# ADCS_Motherboard.net
KiCad netlist of a schematic drawn in EAGLE
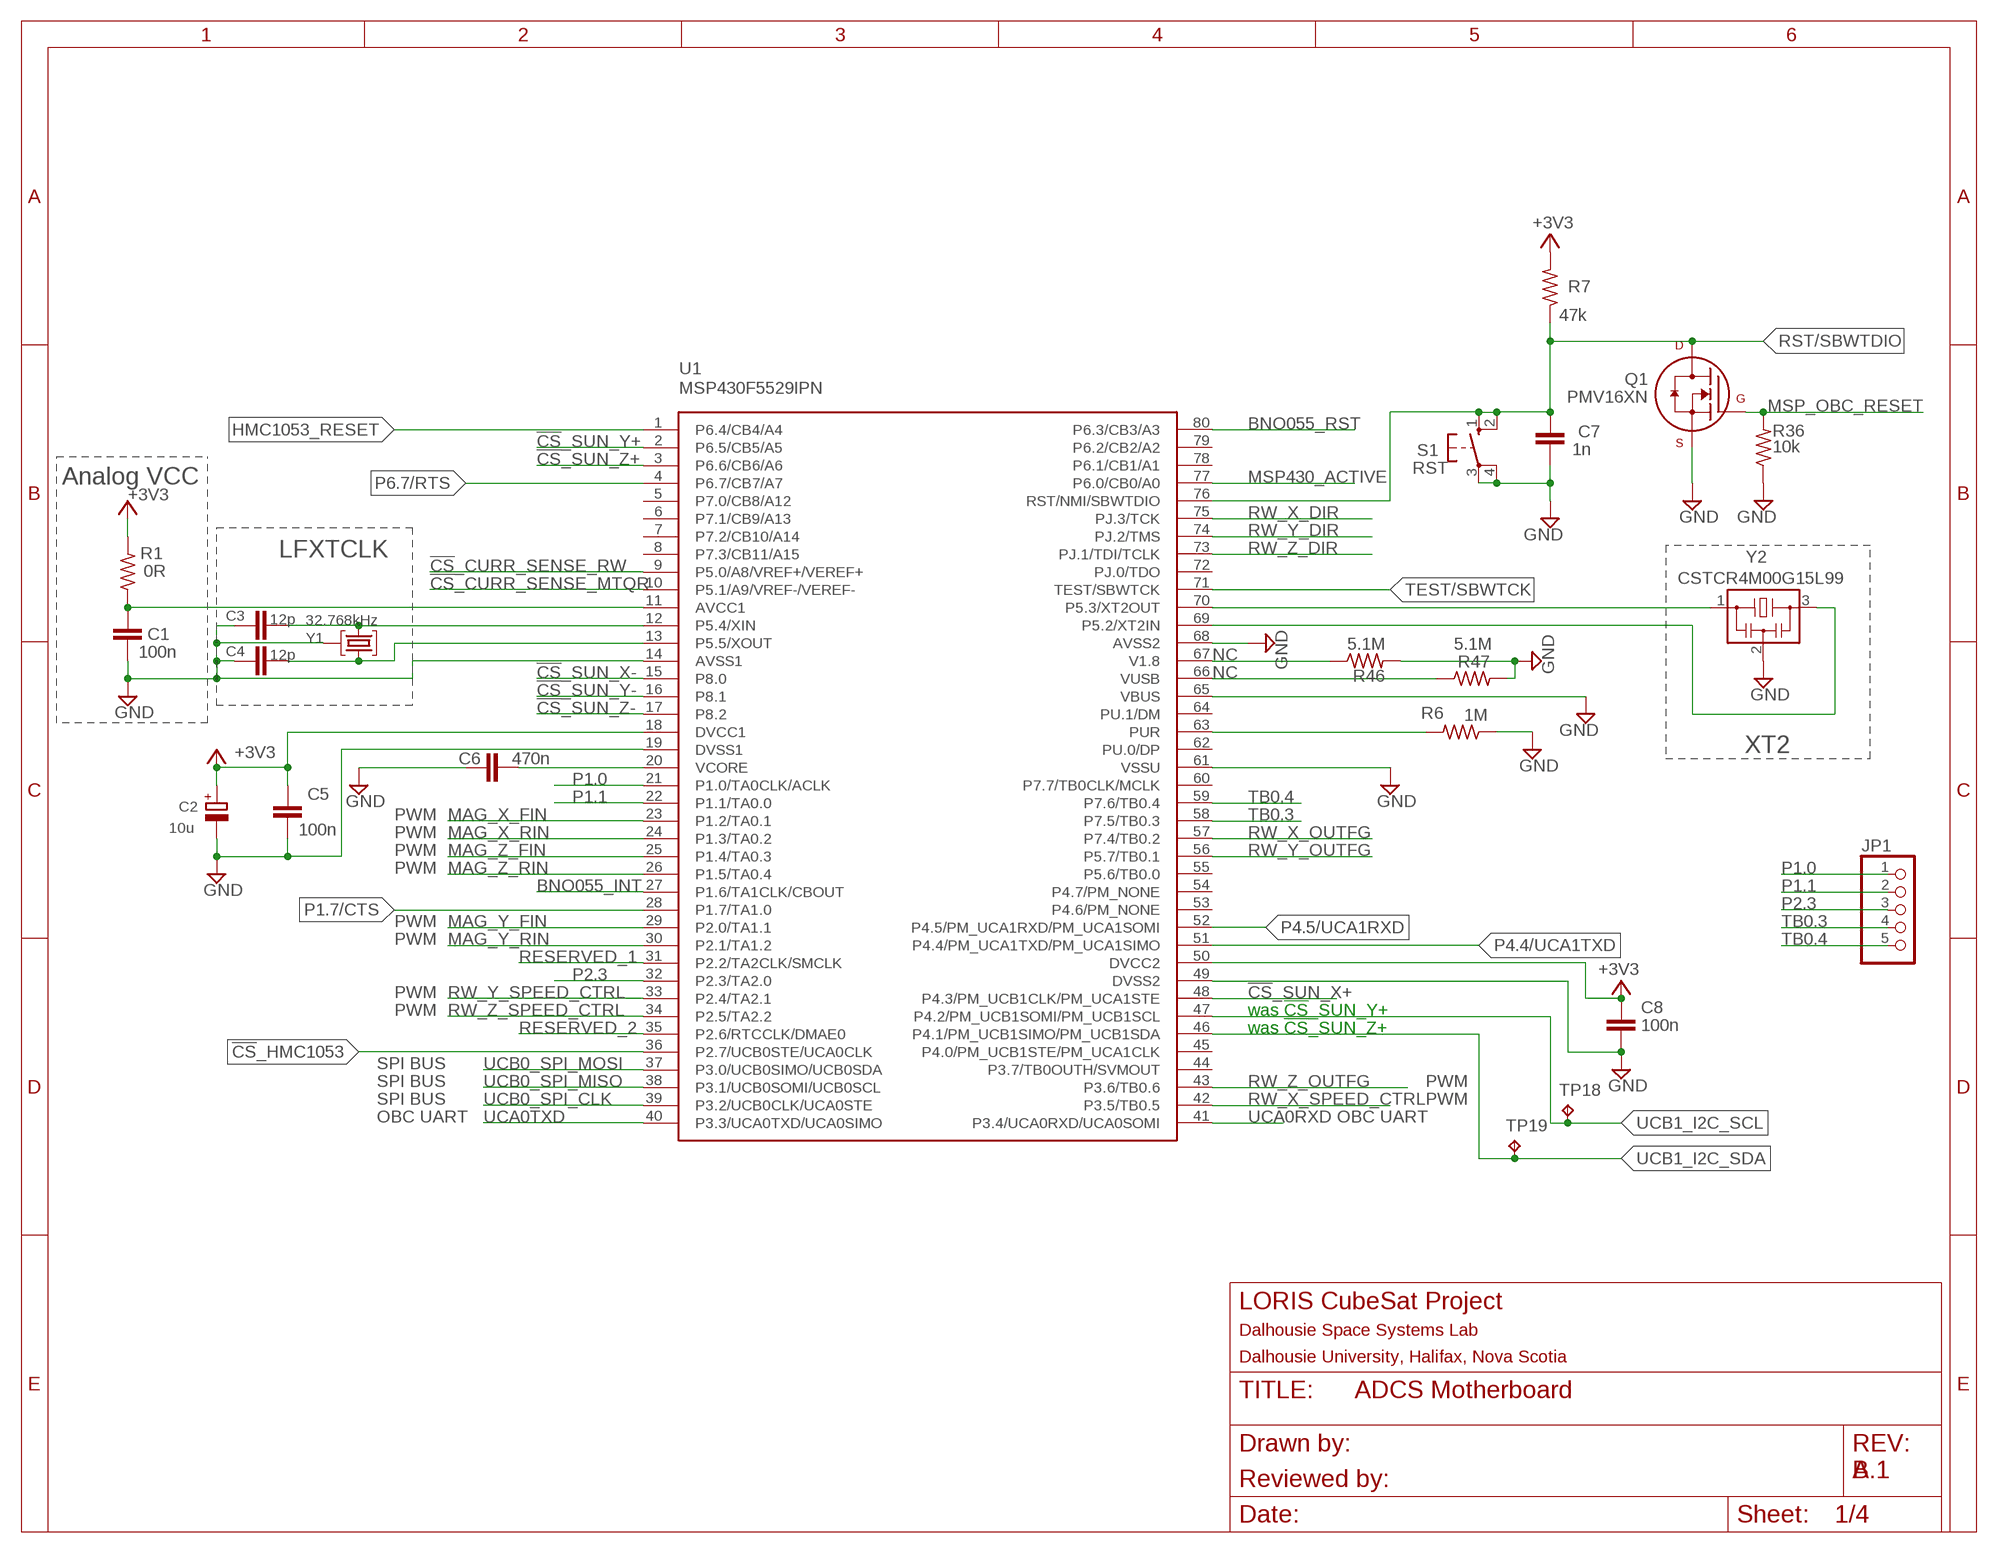
[diagram p0: schematic, sheet 1]
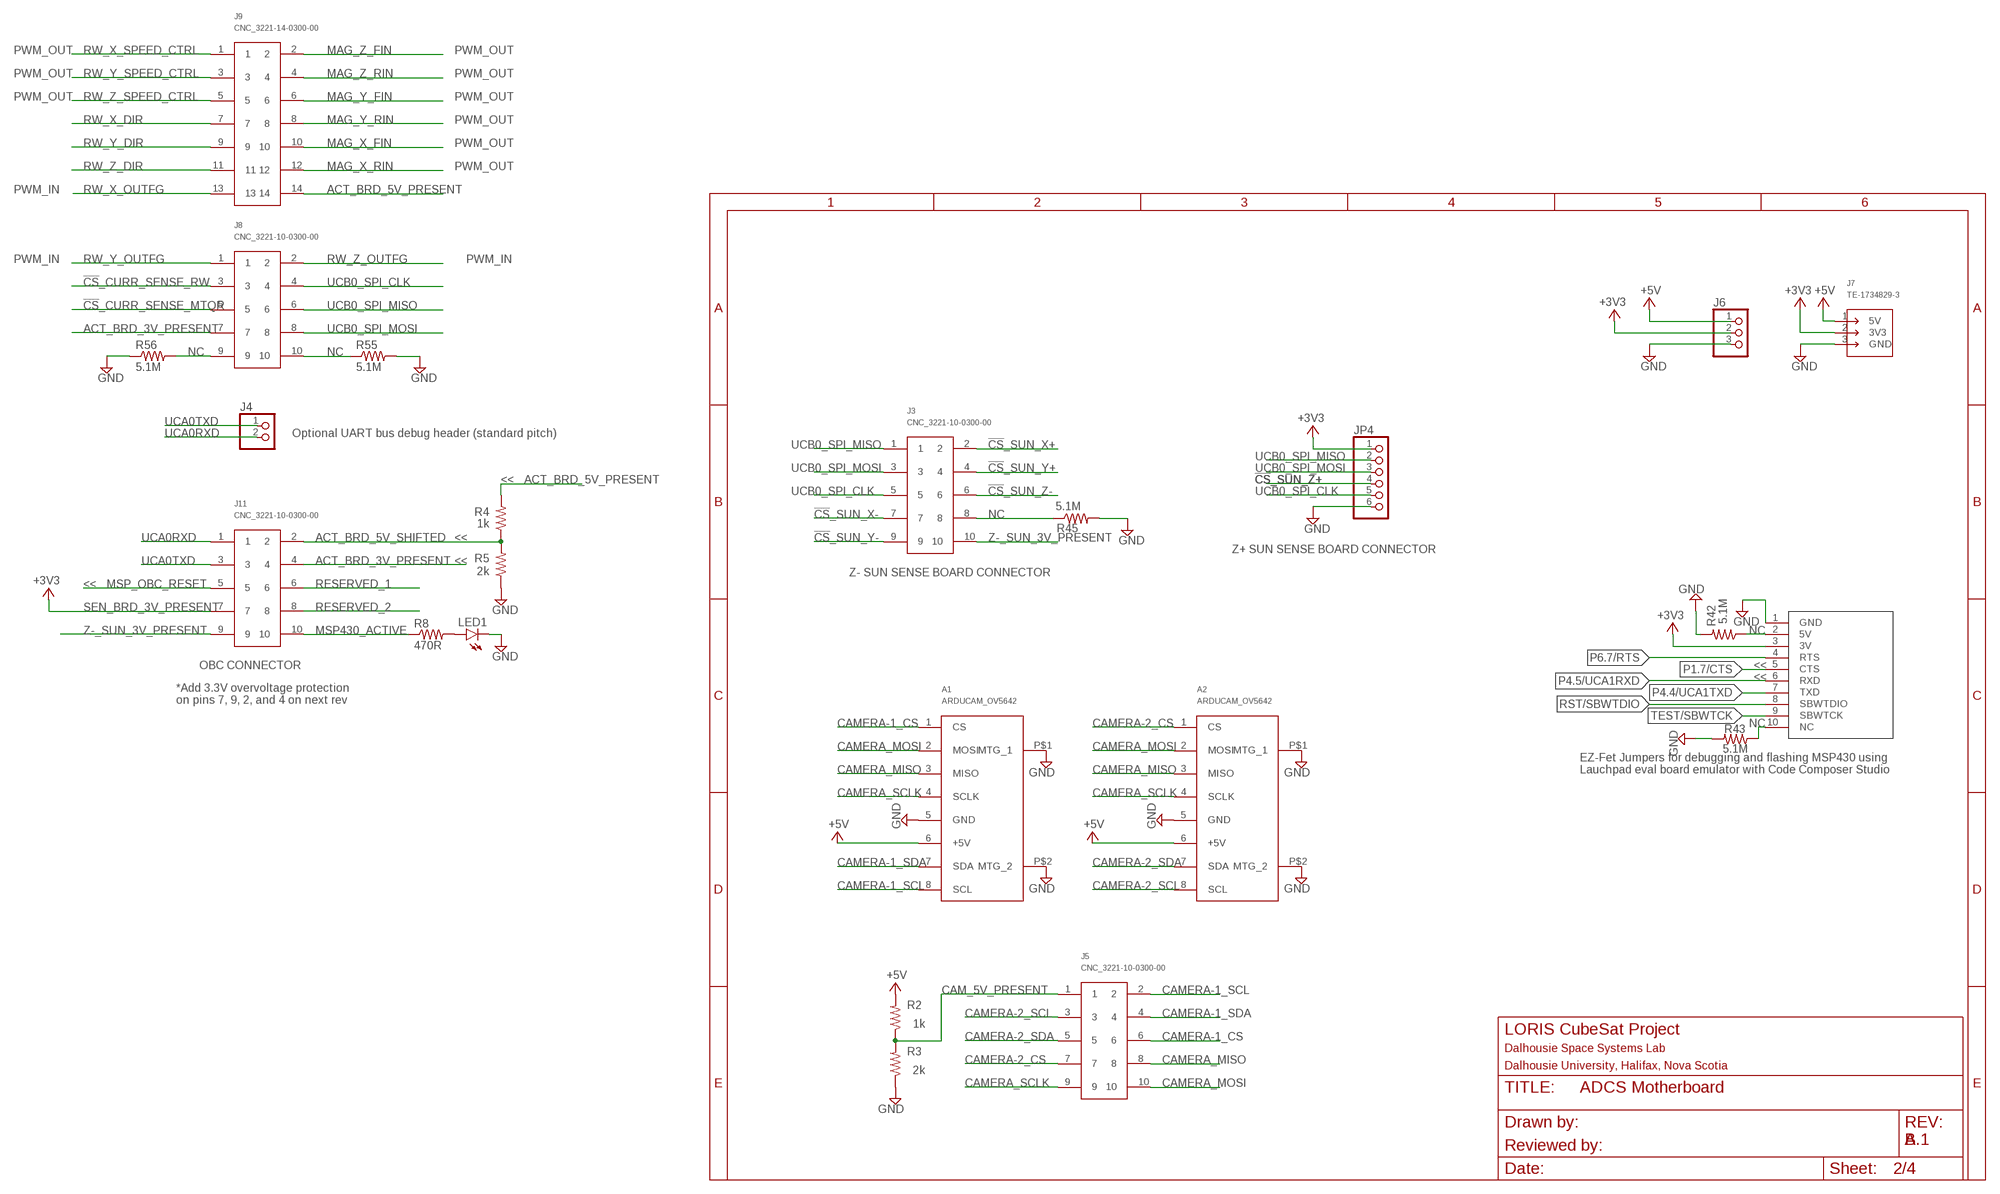
[diagram p1: schematic, sheet 2]
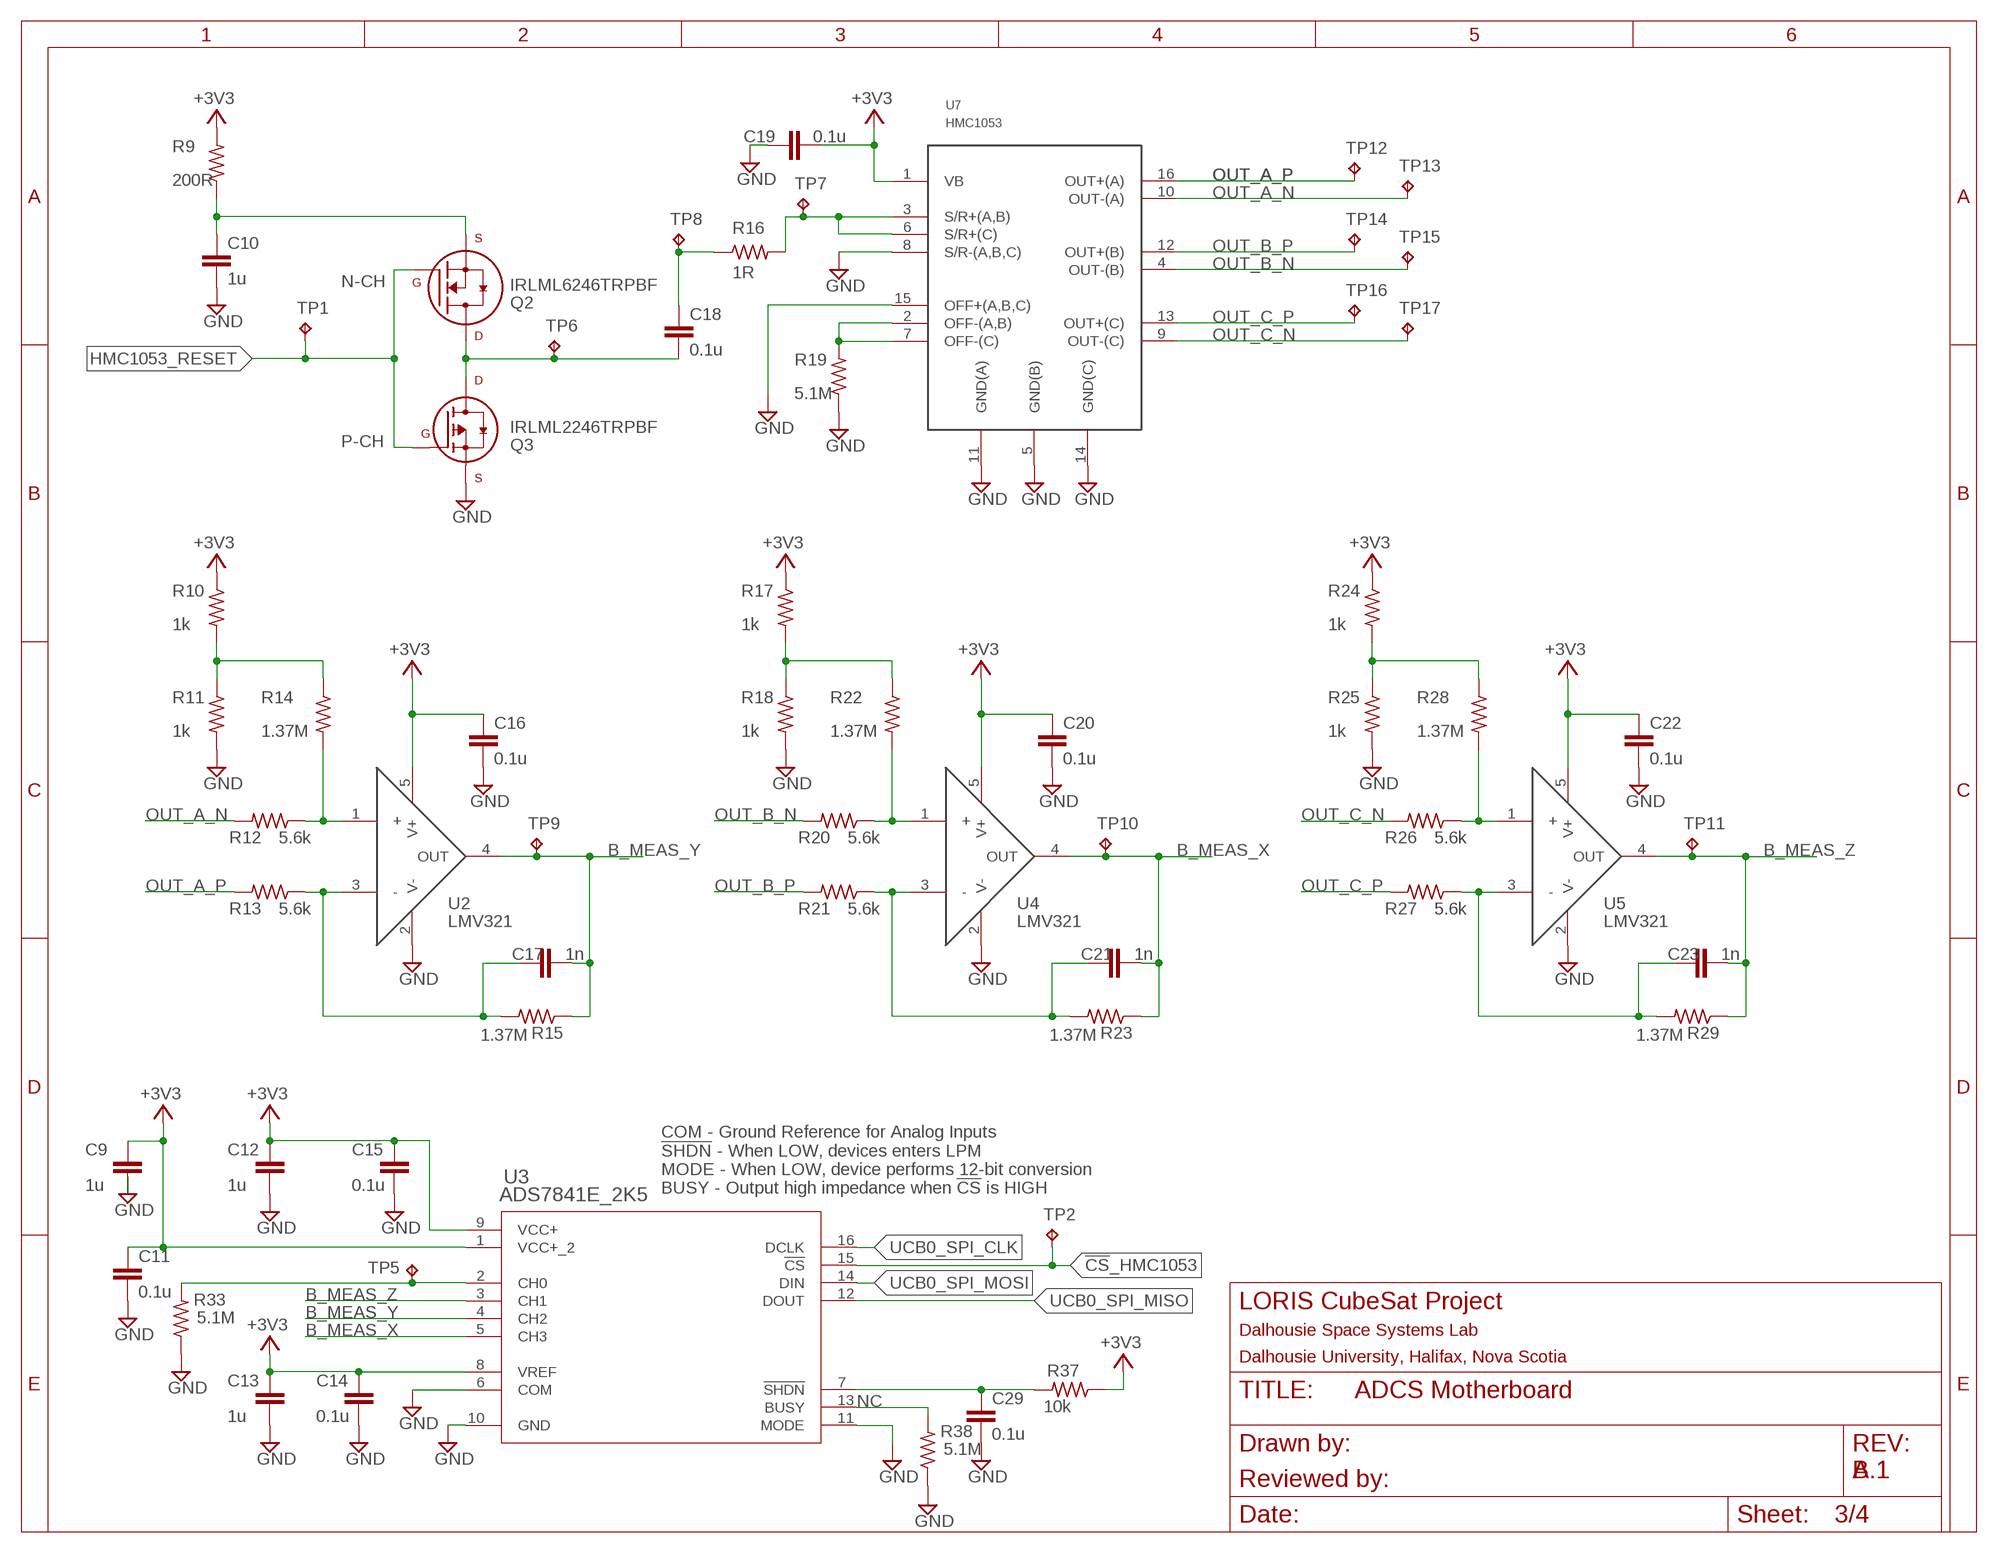
[diagram p2: schematic, sheet 3]
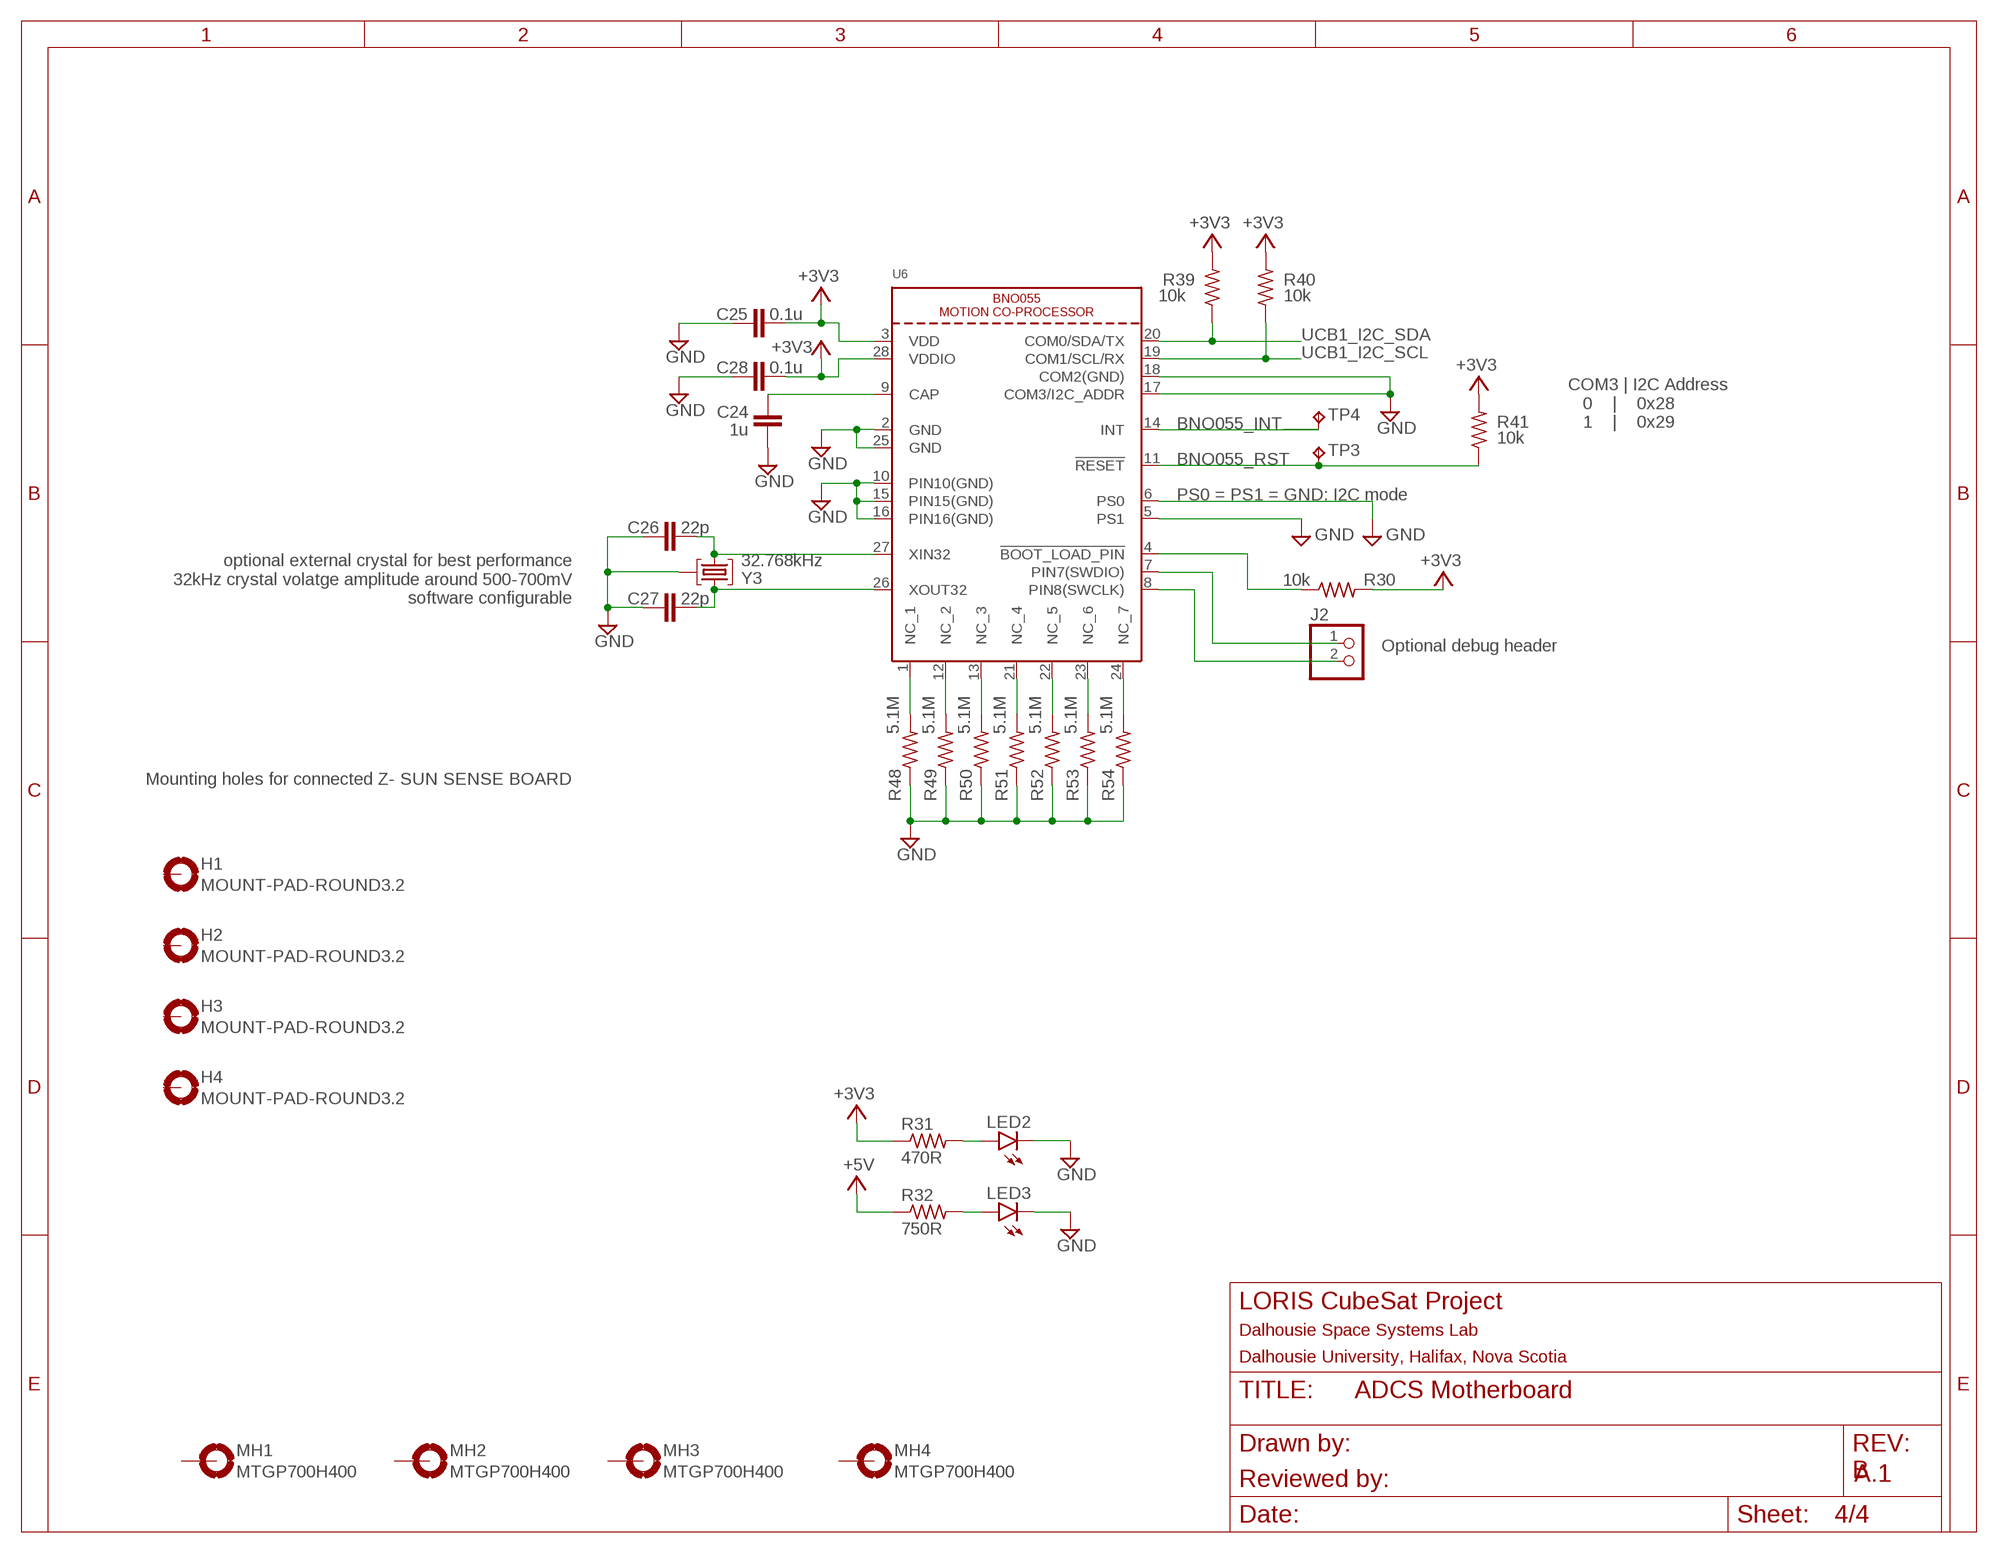
[diagram p3: schematic, sheet 4]

(export (version "E")
  (design (tool "Eeschema 10.0.6"))
  (components
    (comp (ref "C9")
      (value "1u")
      (footprint "eagle-import:C0805")
      (libsource (lib "eagle-import") (part "C-EUC0805"))
    )
    (comp (ref "C10")
      (value "1u")
      (footprint "eagle-import:C0603")
      (libsource (lib "eagle-import") (part "C-EUC0603"))
    )
    (comp (ref "C11")
      (value "0.1u")
      (footprint "eagle-import:C0603")
      (libsource (lib "eagle-import") (part "C-EUC0603"))
    )
    (comp (ref "C12")
      (value "1u")
      (footprint "eagle-import:C0805")
      (libsource (lib "eagle-import") (part "C-EUC0805"))
    )
    (comp (ref "C13")
      (value "1u")
      (footprint "eagle-import:C0805")
      (libsource (lib "eagle-import") (part "C-EUC0805"))
    )
    (comp (ref "C14")
      (value "0.1u")
      (footprint "eagle-import:C0603")
      (libsource (lib "eagle-import") (part "C-EUC0603"))
    )
    (comp (ref "C15")
      (value "0.1u")
      (footprint "eagle-import:C0603")
      (libsource (lib "eagle-import") (part "C-EUC0603"))
    )
    (comp (ref "C16")
      (value "0.1u")
      (footprint "eagle-import:C0603")
      (libsource (lib "eagle-import") (part "C-EUC0603"))
    )
    (comp (ref "C17")
      (value "1n")
      (footprint "eagle-import:C0603")
      (libsource (lib "eagle-import") (part "C-EUC0603"))
    )
    (comp (ref "C18")
      (value "0.1u")
      (footprint "eagle-import:C0805")
      (libsource (lib "eagle-import") (part "C-EUC0805"))
    )
    (comp (ref "C19")
      (value "0.1u")
      (footprint "eagle-import:C0603")
      (libsource (lib "eagle-import") (part "C-EUC0603"))
    )
    (comp (ref "C20")
      (value "0.1u")
      (footprint "eagle-import:C0603")
      (libsource (lib "eagle-import") (part "C-EUC0603"))
    )
    (comp (ref "C21")
      (value "1n")
      (footprint "eagle-import:C0603")
      (libsource (lib "eagle-import") (part "C-EUC0603"))
    )
    (comp (ref "C22")
      (value "0.1u")
      (footprint "eagle-import:C0603")
      (libsource (lib "eagle-import") (part "C-EUC0603"))
    )
    (comp (ref "C23")
      (value "1n")
      (footprint "eagle-import:C0603")
      (libsource (lib "eagle-import") (part "C-EUC0603"))
    )
    (comp (ref "C29")
      (value "0.1u")
      (footprint "eagle-import:C0603")
      (libsource (lib "eagle-import") (part "C-EUC0603"))
    )
    (comp (ref "Q2")
      (value "IRLML6246TRPBF")
      (footprint "eagle-import:SOT23-3P95_237X112L25X40N_MICRO3")
      (libsource (lib "eagle-import") (part "IRLML6246TRPBF"))
    )
    (comp (ref "Q3")
      (value "IRLML2246TRPBF")
      (footprint "eagle-import:SOT23-3P95_237X112L25X40N_MICRO3")
      (libsource (lib "eagle-import") (part "IRLML2246TRPBF"))
    )
    (comp (ref "R9")
      (value "200R")
      (footprint "eagle-import:R0805")
      (libsource (lib "eagle-import") (part "R-US_R0805"))
    )
    (comp (ref "R10")
      (value "1k")
      (footprint "eagle-import:R0603")
      (libsource (lib "eagle-import") (part "R-US_R0603"))
    )
    (comp (ref "R11")
      (value "1k")
      (footprint "eagle-import:R0603")
      (libsource (lib "eagle-import") (part "R-US_R0603"))
    )
    (comp (ref "R12")
      (value "5.6k")
      (footprint "eagle-import:R0603")
      (libsource (lib "eagle-import") (part "R-US_R0603"))
    )
    (comp (ref "R13")
      (value "5.6k")
      (footprint "eagle-import:R0603")
      (libsource (lib "eagle-import") (part "R-US_R0603"))
    )
    (comp (ref "R14")
      (value "1.37M")
      (footprint "eagle-import:R0603")
      (libsource (lib "eagle-import") (part "R-US_R0603"))
    )
    (comp (ref "R15")
      (value "1.37M")
      (footprint "eagle-import:R0603")
      (libsource (lib "eagle-import") (part "R-US_R0603"))
    )
    (comp (ref "R16")
      (value "1R")
      (footprint "eagle-import:R0805")
      (libsource (lib "eagle-import") (part "R-US_R0805"))
    )
    (comp (ref "R17")
      (value "1k")
      (footprint "eagle-import:R0603")
      (libsource (lib "eagle-import") (part "R-US_R0603"))
    )
    (comp (ref "R18")
      (value "1k")
      (footprint "eagle-import:R0603")
      (libsource (lib "eagle-import") (part "R-US_R0603"))
    )
    (comp (ref "R19")
      (value "5.1M")
      (footprint "eagle-import:R0805")
      (libsource (lib "eagle-import") (part "R-US_R0805"))
    )
    (comp (ref "R20")
      (value "5.6k")
      (footprint "eagle-import:R0603")
      (libsource (lib "eagle-import") (part "R-US_R0603"))
    )
    (comp (ref "R21")
      (value "5.6k")
      (footprint "eagle-import:R0603")
      (libsource (lib "eagle-import") (part "R-US_R0603"))
    )
    (comp (ref "R22")
      (value "1.37M")
      (footprint "eagle-import:R0603")
      (libsource (lib "eagle-import") (part "R-US_R0603"))
    )
    (comp (ref "R23")
      (value "1.37M")
      (footprint "eagle-import:R0603")
      (libsource (lib "eagle-import") (part "R-US_R0603"))
    )
    (comp (ref "R24")
      (value "1k")
      (footprint "eagle-import:R0603")
      (libsource (lib "eagle-import") (part "R-US_R0603"))
    )
    (comp (ref "R25")
      (value "1k")
      (footprint "eagle-import:R0603")
      (libsource (lib "eagle-import") (part "R-US_R0603"))
    )
    (comp (ref "R26")
      (value "5.6k")
      (footprint "eagle-import:R0603")
      (libsource (lib "eagle-import") (part "R-US_R0603"))
    )
    (comp (ref "R27")
      (value "5.6k")
      (footprint "eagle-import:R0603")
      (libsource (lib "eagle-import") (part "R-US_R0603"))
    )
    (comp (ref "R28")
      (value "1.37M")
      (footprint "eagle-import:R0603")
      (libsource (lib "eagle-import") (part "R-US_R0603"))
    )
    (comp (ref "R29")
      (value "1.37M")
      (footprint "eagle-import:R0603")
      (libsource (lib "eagle-import") (part "R-US_R0603"))
    )
    (comp (ref "R33")
      (value "5.1M")
      (footprint "eagle-import:R0402")
      (libsource (lib "eagle-import") (part "R-US_R0402"))
    )
    (comp (ref "R37")
      (value "10k")
      (footprint "eagle-import:R0805")
      (libsource (lib "eagle-import") (part "R-US_R0805"))
    )
    (comp (ref "R38")
      (value "5.1M")
      (footprint "eagle-import:R0402")
      (libsource (lib "eagle-import") (part "R-US_R0402"))
    )
    (comp (ref "TP1")
      (value "TESTPOINT")
      (footprint "eagle-import:TP_P76H50")
      (libsource (lib "eagle-import") (part "TESTPOINT"))
    )
    (comp (ref "TP2")
      (value "TESTPOINT")
      (footprint "eagle-import:TP_P76H50")
      (libsource (lib "eagle-import") (part "TESTPOINT"))
    )
    (comp (ref "TP5")
      (value "TESTPOINT")
      (footprint "eagle-import:TP_P76H50")
      (libsource (lib "eagle-import") (part "TESTPOINT"))
    )
    (comp (ref "TP6")
      (value "TESTPOINT")
      (footprint "eagle-import:TP_P76H50")
      (libsource (lib "eagle-import") (part "TESTPOINT"))
    )
    (comp (ref "TP7")
      (value "TESTPOINT")
      (footprint "eagle-import:TP_P76H50")
      (libsource (lib "eagle-import") (part "TESTPOINT"))
    )
    (comp (ref "TP8")
      (value "TESTPOINT")
      (footprint "eagle-import:TP_P76H50")
      (libsource (lib "eagle-import") (part "TESTPOINT"))
    )
    (comp (ref "TP9")
      (value "TESTPOINT")
      (footprint "eagle-import:TP_P76H50")
      (libsource (lib "eagle-import") (part "TESTPOINT"))
    )
    (comp (ref "TP10")
      (value "TESTPOINT")
      (footprint "eagle-import:TP_P76H50")
      (libsource (lib "eagle-import") (part "TESTPOINT"))
    )
    (comp (ref "TP11")
      (value "TESTPOINT")
      (footprint "eagle-import:TP_P76H50")
      (libsource (lib "eagle-import") (part "TESTPOINT"))
    )
    (comp (ref "TP12")
      (value "TESTPOINT")
      (footprint "eagle-import:TP_P76H50")
      (libsource (lib "eagle-import") (part "TESTPOINT"))
    )
    (comp (ref "TP13")
      (value "TESTPOINT")
      (footprint "eagle-import:TP_P76H50")
      (libsource (lib "eagle-import") (part "TESTPOINT"))
    )
    (comp (ref "TP14")
      (value "TESTPOINT")
      (footprint "eagle-import:TP_P76H50")
      (libsource (lib "eagle-import") (part "TESTPOINT"))
    )
    (comp (ref "TP15")
      (value "TESTPOINT")
      (footprint "eagle-import:TP_P76H50")
      (libsource (lib "eagle-import") (part "TESTPOINT"))
    )
    (comp (ref "TP16")
      (value "TESTPOINT")
      (footprint "eagle-import:TP_P76H50")
      (libsource (lib "eagle-import") (part "TESTPOINT"))
    )
    (comp (ref "TP17")
      (value "TESTPOINT")
      (footprint "eagle-import:TP_P76H50")
      (libsource (lib "eagle-import") (part "TESTPOINT"))
    )
    (comp (ref "U2")
      (value "LMV321")
      (footprint "eagle-import:SC70-5P65_210X110L36X22N")
      (libsource (lib "eagle-import") (part "LMV321"))
    )
    (comp (ref "U3")
      (value "ADS7841E_2K5")
      (footprint "eagle-import:DBQ16")
      (fields
        (field (name "GENERIC_PART_NUMBER") "ADS7841")
        (field (name "MANUFACTURER") "Texas Instruments")
      )
      (libsource (lib "eagle-import") (part "ADS7841E_2K5"))
    )
    (comp (ref "U4")
      (value "LMV321")
      (footprint "eagle-import:SC70-5P65_210X110L36X22N")
      (libsource (lib "eagle-import") (part "LMV321"))
    )
    (comp (ref "U5")
      (value "LMV321")
      (footprint "eagle-import:SC70-5P65_210X110L36X22N")
      (libsource (lib "eagle-import") (part "LMV321"))
    )
    (comp (ref "U7")
      (value "HMC1053")
      (footprint "eagle-import:LCCS16P127_736X736X279L127X50N")
      (libsource (lib "eagle-import") (part "HMC1053"))
    )
    (comp (ref "C1")
      (value "100n")
      (footprint "eagle-import:C0402")
      (libsource (lib "eagle-import") (part "C-EUC0402"))
    )
    (comp (ref "C2")
      (value "10u")
      (footprint "eagle-import:A_3216-18R")
      (libsource (lib "eagle-import") (part "POLARIZED_CAP"))
    )
    (comp (ref "C3")
      (value "12p")
      (footprint "eagle-import:C0402")
      (libsource (lib "eagle-import") (part "C-EUC0402"))
    )
    (comp (ref "C4")
      (value "12p")
      (footprint "eagle-import:C0402")
      (libsource (lib "eagle-import") (part "C-EUC0402"))
    )
    (comp (ref "C5")
      (value "100n")
      (footprint "eagle-import:C0402")
      (libsource (lib "eagle-import") (part "C-EUC0402"))
    )
    (comp (ref "C6")
      (value "470n")
      (footprint "eagle-import:C0402")
      (libsource (lib "eagle-import") (part "C-EUC0402"))
    )
    (comp (ref "C7")
      (value "1n")
      (footprint "eagle-import:C0402")
      (libsource (lib "eagle-import") (part "C-EUC0402"))
    )
    (comp (ref "C8")
      (value "100n")
      (footprint "eagle-import:C0402")
      (libsource (lib "eagle-import") (part "C-EUC0402"))
    )
    (comp (ref "JP1")
      (value "PINHD-1X5")
      (footprint "eagle-import:1X05")
      (libsource (lib "eagle-import") (part "PINHD-1X5"))
    )
    (comp (ref "Q1")
      (value "PMV16XN")
      (footprint "eagle-import:SOT23-3P95_230X110L20X43N_PMV16XN")
      (libsource (lib "eagle-import") (part "PMV16XN"))
    )
    (comp (ref "R1")
      (value "0R")
      (footprint "eagle-import:R0402")
      (libsource (lib "eagle-import") (part "R-US_R0402"))
    )
    (comp (ref "R6")
      (value "1M")
      (footprint "eagle-import:R0603")
      (libsource (lib "eagle-import") (part "R-US_R0603"))
    )
    (comp (ref "R7")
      (value "47k")
      (footprint "eagle-import:R0402")
      (libsource (lib "eagle-import") (part "R-US_R0402"))
    )
    (comp (ref "R36")
      (value "10k")
      (footprint "eagle-import:R0603")
      (libsource (lib "eagle-import") (part "R-US_R0603"))
    )
    (comp (ref "R46")
      (value "5.1M")
      (footprint "eagle-import:R0402")
      (libsource (lib "eagle-import") (part "R-US_R0402"))
    )
    (comp (ref "R47")
      (value "5.1M")
      (footprint "eagle-import:R0402")
      (libsource (lib "eagle-import") (part "R-US_R0402"))
    )
    (comp (ref "S1")
      (value "RST")
      (footprint "eagle-import:B3F-10XX")
      (fields (field (name "MPN") "B3F-1000"))
      (libsource (lib "eagle-import") (part "10-XX"))
    )
    (comp (ref "TP18")
      (value "TESTPOINT")
      (footprint "eagle-import:TP_P76H50")
      (libsource (lib "eagle-import") (part "TESTPOINT"))
    )
    (comp (ref "TP19")
      (value "TESTPOINT")
      (footprint "eagle-import:TP_P76H50")
      (libsource (lib "eagle-import") (part "TESTPOINT"))
    )
    (comp (ref "U1")
      (value "MSP430F5529IPN")
      (footprint "eagle-import:QFP80P50_1400X1400X160L60X22N")
      (libsource (lib "eagle-import") (part "MSP430F5529IPN"))
    )
    (comp (ref "Y1")
      (value "32.768kHz")
      (footprint "eagle-import:MS3V-T1R")
      (libsource (lib "eagle-import") (part "MS3V-T1R"))
    )
    (comp (ref "Y2")
      (value "CSTCR4M00G15L99")
      (footprint "eagle-import:MURATA-FILTER_CSTCR")
      (fields (field (name "MPN") "CSTCR6M00G53-R0"))
      (libsource (lib "eagle-import") (part "CSTCR4M00G15L996M00G53Z"))
    )
    (comp (ref "C24")
      (value "1u")
      (footprint "eagle-import:C0402")
      (libsource (lib "eagle-import") (part "C-EUC0402"))
    )
    (comp (ref "C25")
      (value "0.1u")
      (footprint "eagle-import:C0402")
      (libsource (lib "eagle-import") (part "C-EUC0402"))
    )
    (comp (ref "C26")
      (value "22p")
      (footprint "eagle-import:C0402")
      (libsource (lib "eagle-import") (part "C-EUC0402"))
    )
    (comp (ref "C27")
      (value "22p")
      (footprint "eagle-import:C0402")
      (libsource (lib "eagle-import") (part "C-EUC0402"))
    )
    (comp (ref "C28")
      (value "0.1u")
      (footprint "eagle-import:C0402")
      (libsource (lib "eagle-import") (part "C-EUC0402"))
    )
    (comp (ref "H1")
      (value "MOUNT-PAD-ROUND3.2")
      (footprint "eagle-import:3,2-PAD")
      (libsource (lib "eagle-import") (part "MOUNT-PAD-ROUND3.2"))
    )
    (comp (ref "H2")
      (value "MOUNT-PAD-ROUND3.2")
      (footprint "eagle-import:3,2-PAD")
      (libsource (lib "eagle-import") (part "MOUNT-PAD-ROUND3.2"))
    )
    (comp (ref "H3")
      (value "MOUNT-PAD-ROUND3.2")
      (footprint "eagle-import:3,2-PAD")
      (libsource (lib "eagle-import") (part "MOUNT-PAD-ROUND3.2"))
    )
    (comp (ref "H4")
      (value "MOUNT-PAD-ROUND3.2")
      (footprint "eagle-import:3,2-PAD")
      (libsource (lib "eagle-import") (part "MOUNT-PAD-ROUND3.2"))
    )
    (comp (ref "J2")
      (value "HDR_1X2_")
      (footprint "eagle-import:1X02")
      (libsource (lib "eagle-import") (part "HDR_1X2_"))
    )
    (comp (ref "LED2")
      (value "LEDCHIP-LED0603")
      (footprint "eagle-import:CHIP-LED0603")
      (libsource (lib "eagle-import") (part "LEDCHIP-LED0603"))
    )
    (comp (ref "LED3")
      (value "LEDCHIP-LED0603")
      (footprint "eagle-import:CHIP-LED0603")
      (libsource (lib "eagle-import") (part "LEDCHIP-LED0603"))
    )
    (comp (ref "MH1")
      (value "MTGP700H400")
      (footprint "eagle-import:MTGP700H400")
      (libsource (lib "eagle-import") (part "MTGP700H400"))
    )
    (comp (ref "MH2")
      (value "MTGP700H400")
      (footprint "eagle-import:MTGP700H400")
      (libsource (lib "eagle-import") (part "MTGP700H400"))
    )
    (comp (ref "MH3")
      (value "MTGP700H400")
      (footprint "eagle-import:MTGP700H400")
      (libsource (lib "eagle-import") (part "MTGP700H400"))
    )
    (comp (ref "MH4")
      (value "MTGP700H400")
      (footprint "eagle-import:MTGP700H400")
      (libsource (lib "eagle-import") (part "MTGP700H400"))
    )
    (comp (ref "R30")
      (value "10k")
      (footprint "eagle-import:R0402")
      (libsource (lib "eagle-import") (part "R-US_R0402"))
    )
    (comp (ref "R31")
      (value "470R")
      (footprint "eagle-import:R0603")
      (libsource (lib "eagle-import") (part "R-US_R0603"))
    )
    (comp (ref "R32")
      (value "750R")
      (footprint "eagle-import:R0603")
      (libsource (lib "eagle-import") (part "R-US_R0603"))
    )
    (comp (ref "R39")
      (value "10k")
      (footprint "eagle-import:R0402")
      (libsource (lib "eagle-import") (part "R-US_R0402"))
    )
    (comp (ref "R40")
      (value "10k")
      (footprint "eagle-import:R0402")
      (libsource (lib "eagle-import") (part "R-US_R0402"))
    )
    (comp (ref "R41")
      (value "10k")
      (footprint "eagle-import:R0402")
      (libsource (lib "eagle-import") (part "R-US_R0402"))
    )
    (comp (ref "R48")
      (value "5.1M")
      (footprint "eagle-import:R0402")
      (libsource (lib "eagle-import") (part "R-US_R0402"))
    )
    (comp (ref "R49")
      (value "5.1M")
      (footprint "eagle-import:R0402")
      (libsource (lib "eagle-import") (part "R-US_R0402"))
    )
    (comp (ref "R50")
      (value "5.1M")
      (footprint "eagle-import:R0402")
      (libsource (lib "eagle-import") (part "R-US_R0402"))
    )
    (comp (ref "R51")
      (value "5.1M")
      (footprint "eagle-import:R0402")
      (libsource (lib "eagle-import") (part "R-US_R0402"))
    )
    (comp (ref "R52")
      (value "5.1M")
      (footprint "eagle-import:R0402")
      (libsource (lib "eagle-import") (part "R-US_R0402"))
    )
    (comp (ref "R53")
      (value "5.1M")
      (footprint "eagle-import:R0402")
      (libsource (lib "eagle-import") (part "R-US_R0402"))
    )
    (comp (ref "R54")
      (value "5.1M")
      (footprint "eagle-import:R0402")
      (libsource (lib "eagle-import") (part "R-US_R0402"))
    )
    (comp (ref "TP3")
      (value "TESTPOINT")
      (footprint "eagle-import:TP_P76H50")
      (libsource (lib "eagle-import") (part "TESTPOINT"))
    )
    (comp (ref "TP4")
      (value "TESTPOINT")
      (footprint "eagle-import:TP_P76H50")
      (libsource (lib "eagle-import") (part "TESTPOINT"))
    )
    (comp (ref "U6")
      (value "BNO055")
      (footprint "eagle-import:BNO055")
      (libsource (lib "eagle-import") (part "BNO055"))
    )
    (comp (ref "Y3")
      (value "32.768kHz")
      (footprint "eagle-import:MS3V-T1R")
      (libsource (lib "eagle-import") (part "MS3V-T1R"))
    )
    (comp (ref "A1")
      (value "ARDUCAM_OV5642")
      (footprint "eagle-import:ARDUCAM")
      (libsource (lib "eagle-import") (part "ARDUCAM_OV5642"))
    )
    (comp (ref "A2")
      (value "ARDUCAM_OV5642")
      (footprint "eagle-import:ARDUCAM")
      (libsource (lib "eagle-import") (part "ARDUCAM_OV5642"))
    )
    (comp (ref "J1")
      (value "HDR_10_EZFET_DEBUGGER")
      (footprint "eagle-import:HDRV10W66P254_10X1_2540X254H858")
      (libsource (lib "eagle-import") (part "HDR_10_EZFET_DEBUGGER"))
    )
    (comp (ref "J3")
      (value "CNC_3221-10-0300-00")
      (footprint "eagle-import:CNC_3221-10-0300-00")
      (libsource (lib "eagle-import") (part "CNC_3221-10-0300-00"))
    )
    (comp (ref "J4")
      (value "HDR_1X2_")
      (footprint "eagle-import:1X02")
      (libsource (lib "eagle-import") (part "HDR_1X2_"))
    )
    (comp (ref "J5")
      (value "CNC_3221-10-0300-00")
      (footprint "eagle-import:CNC_3221-10-0300-00")
      (libsource (lib "eagle-import") (part "CNC_3221-10-0300-00"))
    )
    (comp (ref "J6")
      (value "PINHD-1X3")
      (footprint "eagle-import:1X03")
      (libsource (lib "eagle-import") (part "PINHD-1X3"))
    )
    (comp (ref "J7")
      (value "TE-1734829-3")
      (footprint "eagle-import:TE-1734829-3")
      (libsource (lib "eagle-import") (part "TE-1734829-3"))
    )
    (comp (ref "J8")
      (value "CNC_3221-10-0300-00")
      (footprint "eagle-import:CNC_3221-10-0300-00")
      (libsource (lib "eagle-import") (part "CNC_3221-10-0300-00"))
    )
    (comp (ref "J9")
      (value "CNC_3221-14-0300-00")
      (footprint "eagle-import:CNC_3221-14-0300-00")
      (libsource (lib "eagle-import") (part "CNC_3221-14-0300-00"))
    )
    (comp (ref "J11")
      (value "CNC_3221-10-0300-00")
      (footprint "eagle-import:CNC_3221-10-0300-00")
      (libsource (lib "eagle-import") (part "CNC_3221-10-0300-00"))
    )
    (comp (ref "JP4")
      (value "PINHD-1X6")
      (footprint "eagle-import:1X06")
      (libsource (lib "eagle-import") (part "PINHD-1X6"))
    )
    (comp (ref "LED1")
      (value "LEDCHIP-LED0603")
      (footprint "eagle-import:CHIP-LED0603")
      (libsource (lib "eagle-import") (part "LEDCHIP-LED0603"))
    )
    (comp (ref "R2")
      (value "1k")
      (footprint "eagle-import:R0603")
      (libsource (lib "eagle-import") (part "R-US_R0603"))
    )
    (comp (ref "R3")
      (value "2k")
      (footprint "eagle-import:R0603")
      (libsource (lib "eagle-import") (part "R-US_R0603"))
    )
    (comp (ref "R4")
      (value "1k")
      (footprint "eagle-import:R0603")
      (libsource (lib "eagle-import") (part "R-US_R0603"))
    )
    (comp (ref "R5")
      (value "2k")
      (footprint "eagle-import:R0603")
      (libsource (lib "eagle-import") (part "R-US_R0603"))
    )
    (comp (ref "R8")
      (value "470R")
      (footprint "eagle-import:R0603")
      (libsource (lib "eagle-import") (part "R-US_R0603"))
    )
    (comp (ref "R42")
      (value "5.1M")
      (footprint "eagle-import:R0402")
      (libsource (lib "eagle-import") (part "R-US_R0402"))
    )
    (comp (ref "R43")
      (value "5.1M")
      (footprint "eagle-import:R0402")
      (libsource (lib "eagle-import") (part "R-US_R0402"))
    )
    (comp (ref "R45")
      (value "5.1M")
      (footprint "eagle-import:R0402")
      (libsource (lib "eagle-import") (part "R-US_R0402"))
    )
    (comp (ref "R55")
      (value "5.1M")
      (footprint "eagle-import:R0603")
      (libsource (lib "eagle-import") (part "R-US_R0603"))
    )
    (comp (ref "R56")
      (value "5.1M")
      (footprint "eagle-import:R0603")
      (libsource (lib "eagle-import") (part "R-US_R0603"))
    )
  )
  (nets
    (net (code "1") (name "+3V3") (class "Default")
      (node (ref "C11") (pin "1") (pinfunction "1_1") (pintype "passive"))
      (node (ref "C12") (pin "1") (pinfunction "1_1") (pintype "passive"))
      (node (ref "C13") (pin "1") (pinfunction "1_1") (pintype "passive"))
      (node (ref "C14") (pin "1") (pinfunction "1_1") (pintype "passive"))
      (node (ref "C15") (pin "1") (pinfunction "1_1") (pintype "passive"))
      (node (ref "C16") (pin "1") (pinfunction "1_1") (pintype "passive"))
      (node (ref "C19") (pin "1") (pinfunction "1_1") (pintype "passive"))
      (node (ref "C2") (pin "+") (pinfunction "+_+") (pintype "passive"))
      (node (ref "C20") (pin "1") (pinfunction "1_1") (pintype "passive"))
      (node (ref "C22") (pin "1") (pinfunction "1_1") (pintype "passive"))
      (node (ref "C25") (pin "2") (pinfunction "2_2") (pintype "passive"))
      (node (ref "C28") (pin "2") (pinfunction "2_2") (pintype "passive"))
      (node (ref "C5") (pin "2") (pinfunction "2_2") (pintype "passive"))
      (node (ref "C8") (pin "1") (pinfunction "1_1") (pintype "passive"))
      (node (ref "C9") (pin "1") (pinfunction "1_1") (pintype "passive"))
      (node (ref "J1") (pin "3") (pinfunction "3V_3") (pintype "bidirectional"))
      (node (ref "J11") (pin "7") (pinfunction "7_7") (pintype "bidirectional"))
      (node (ref "J6") (pin "2") (pinfunction "2_2") (pintype "passive"))
      (node (ref "J7") (pin "2") (pinfunction "3V3_2") (pintype "bidirectional"))
      (node (ref "JP4") (pin "1") (pinfunction "1_1") (pintype "passive"))
      (node (ref "R1") (pin "2") (pinfunction "2_2") (pintype "passive"))
      (node (ref "R10") (pin "1") (pinfunction "1_1") (pintype "passive"))
      (node (ref "R17") (pin "1") (pinfunction "1_1") (pintype "passive"))
      (node (ref "R24") (pin "1") (pinfunction "1_1") (pintype "passive"))
      (node (ref "R30") (pin "2") (pinfunction "2_2") (pintype "passive"))
      (node (ref "R31") (pin "1") (pinfunction "1_1") (pintype "passive"))
      (node (ref "R37") (pin "1") (pinfunction "1_1") (pintype "passive"))
      (node (ref "R39") (pin "2") (pinfunction "2_2") (pintype "passive"))
      (node (ref "R40") (pin "2") (pinfunction "2_2") (pintype "passive"))
      (node (ref "R41") (pin "2") (pinfunction "2_2") (pintype "passive"))
      (node (ref "R7") (pin "2") (pinfunction "2_2") (pintype "passive"))
      (node (ref "R9") (pin "2") (pinfunction "2_2") (pintype "passive"))
      (node (ref "U1") (pin "18") (pinfunction "DVCC1_18") (pintype "bidirectional"))
      (node (ref "U1") (pin "50") (pinfunction "DVCC2_50") (pintype "bidirectional"))
      (node (ref "U2") (pin "5") (pinfunction "V+_5") (pintype "bidirectional"))
      (node (ref "U3") (pin "1") (pinfunction "VCC+_2_1") (pintype "power_in"))
      (node (ref "U3") (pin "8") (pinfunction "VREF_8") (pintype "input"))
      (node (ref "U3") (pin "9") (pinfunction "VCC+_9") (pintype "power_in"))
      (node (ref "U4") (pin "5") (pinfunction "V+_5") (pintype "bidirectional"))
      (node (ref "U5") (pin "5") (pinfunction "V+_5") (pintype "bidirectional"))
      (node (ref "U6") (pin "28") (pinfunction "VDDIO_28") (pintype "power_in"))
      (node (ref "U6") (pin "3") (pinfunction "VDD_3") (pintype "power_in"))
      (node (ref "U7") (pin "1") (pinfunction "VB_1") (pintype "bidirectional"))
    )
    (net (code "2") (name "+5V") (class "Default")
      (node (ref "A1") (pin "6") (pinfunction "+5V_6") (pintype "bidirectional"))
      (node (ref "A2") (pin "6") (pinfunction "+5V_6") (pintype "bidirectional"))
      (node (ref "J6") (pin "1") (pinfunction "1_1") (pintype "passive"))
      (node (ref "J7") (pin "1") (pinfunction "5V_1") (pintype "bidirectional"))
      (node (ref "R2") (pin "2") (pinfunction "2_2") (pintype "passive"))
      (node (ref "R32") (pin "1") (pinfunction "1_1") (pintype "passive"))
    )
    (net (code "3") (name "ACT_BRD_3V_PRESENT") (class "Default")
      (node (ref "J11") (pin "4") (pinfunction "4_4") (pintype "bidirectional"))
      (node (ref "J8") (pin "7") (pinfunction "7_7") (pintype "bidirectional"))
    )
    (net (code "4") (name "ACT_BRD_5V_PRESENT") (class "Default")
      (node (ref "J9") (pin "14") (pinfunction "14_14") (pintype "bidirectional"))
      (node (ref "R4") (pin "2") (pinfunction "2_2") (pintype "passive"))
    )
    (net (code "5") (name "ACT_BRD_5V_SHIFTED") (class "Default")
      (node (ref "J11") (pin "2") (pinfunction "2_2") (pintype "bidirectional"))
      (node (ref "R4") (pin "1") (pinfunction "1_1") (pintype "passive"))
      (node (ref "R5") (pin "2") (pinfunction "2_2") (pintype "passive"))
    )
    (net (code "6") (name "BNO055_INT") (class "Default")
      (node (ref "TP4") (pin "1") (pinfunction "TP_1") (pintype "input"))
      (node (ref "U1") (pin "27") (pinfunction "P1.6/TA1CLK/CBOUT_27") (pintype "bidirectional"))
      (node (ref "U6") (pin "14") (pinfunction "INT_14") (pintype "output"))
    )
    (net (code "7") (name "BNO055_RST") (class "Default")
      (node (ref "R41") (pin "1") (pinfunction "1_1") (pintype "passive"))
      (node (ref "TP3") (pin "1") (pinfunction "TP_1") (pintype "input"))
      (node (ref "U1") (pin "80") (pinfunction "P6.3/CB3/A3_80") (pintype "bidirectional"))
      (node (ref "U6") (pin "11") (pinfunction "~{RESET}_11") (pintype "bidirectional"))
    )
    (net (code "8") (name "B_MEAS_X") (class "Default")
      (node (ref "C21") (pin "2") (pinfunction "2_2") (pintype "passive"))
      (node (ref "R23") (pin "1") (pinfunction "1_1") (pintype "passive"))
      (node (ref "TP10") (pin "1") (pinfunction "TP_1") (pintype "input"))
      (node (ref "U3") (pin "5") (pinfunction "CH3_5") (pintype "input"))
      (node (ref "U4") (pin "4") (pinfunction "OUT_4") (pintype "bidirectional"))
    )
    (net (code "9") (name "B_MEAS_Y") (class "Default")
      (node (ref "C17") (pin "2") (pinfunction "2_2") (pintype "passive"))
      (node (ref "R15") (pin "1") (pinfunction "1_1") (pintype "passive"))
      (node (ref "TP9") (pin "1") (pinfunction "TP_1") (pintype "input"))
      (node (ref "U2") (pin "4") (pinfunction "OUT_4") (pintype "bidirectional"))
      (node (ref "U3") (pin "4") (pinfunction "CH2_4") (pintype "input"))
    )
    (net (code "10") (name "B_MEAS_Z") (class "Default")
      (node (ref "C23") (pin "2") (pinfunction "2_2") (pintype "passive"))
      (node (ref "R29") (pin "1") (pinfunction "1_1") (pintype "passive"))
      (node (ref "TP11") (pin "1") (pinfunction "TP_1") (pintype "input"))
      (node (ref "U3") (pin "3") (pinfunction "CH1_3") (pintype "input"))
      (node (ref "U5") (pin "4") (pinfunction "OUT_4") (pintype "bidirectional"))
    )
    (net (code "11") (name "CAMERA-1_CS") (class "Default")
      (node (ref "A1") (pin "1") (pinfunction "CS_1") (pintype "bidirectional"))
      (node (ref "J5") (pin "6") (pinfunction "6_6") (pintype "bidirectional"))
    )
    (net (code "12") (name "CAMERA-1_SCL") (class "Default")
      (node (ref "A1") (pin "8") (pinfunction "SCL_8") (pintype "bidirectional"))
      (node (ref "J5") (pin "2") (pinfunction "2_2") (pintype "bidirectional"))
    )
    (net (code "13") (name "CAMERA-1_SDA") (class "Default")
      (node (ref "A1") (pin "7") (pinfunction "SDA_7") (pintype "bidirectional"))
      (node (ref "J5") (pin "4") (pinfunction "4_4") (pintype "bidirectional"))
    )
    (net (code "14") (name "CAMERA-2_CS") (class "Default")
      (node (ref "A2") (pin "1") (pinfunction "CS_1") (pintype "bidirectional"))
      (node (ref "J5") (pin "7") (pinfunction "7_7") (pintype "bidirectional"))
    )
    (net (code "15") (name "CAMERA-2_SCL") (class "Default")
      (node (ref "A2") (pin "8") (pinfunction "SCL_8") (pintype "bidirectional"))
      (node (ref "J5") (pin "3") (pinfunction "3_3") (pintype "bidirectional"))
    )
    (net (code "16") (name "CAMERA-2_SDA") (class "Default")
      (node (ref "A2") (pin "7") (pinfunction "SDA_7") (pintype "bidirectional"))
      (node (ref "J5") (pin "5") (pinfunction "5_5") (pintype "bidirectional"))
    )
    (net (code "17") (name "CAMERA_MISO") (class "Default")
      (node (ref "A1") (pin "3") (pinfunction "MISO_3") (pintype "bidirectional"))
      (node (ref "A2") (pin "3") (pinfunction "MISO_3") (pintype "bidirectional"))
      (node (ref "J5") (pin "8") (pinfunction "8_8") (pintype "bidirectional"))
    )
    (net (code "18") (name "CAMERA_MOSI") (class "Default")
      (node (ref "A1") (pin "2") (pinfunction "MOSI_2") (pintype "bidirectional"))
      (node (ref "A2") (pin "2") (pinfunction "MOSI_2") (pintype "bidirectional"))
      (node (ref "J5") (pin "10") (pinfunction "10_10") (pintype "bidirectional"))
    )
    (net (code "19") (name "CAMERA_SCLK") (class "Default")
      (node (ref "A1") (pin "4") (pinfunction "SCLK_4") (pintype "bidirectional"))
      (node (ref "A2") (pin "4") (pinfunction "SCLK_4") (pintype "bidirectional"))
      (node (ref "J5") (pin "9") (pinfunction "9_9") (pintype "bidirectional"))
    )
    (net (code "20") (name "CAM_5V_PRESENT") (class "Default")
      (node (ref "J5") (pin "1") (pinfunction "1_1") (pintype "bidirectional"))
      (node (ref "R2") (pin "1") (pinfunction "1_1") (pintype "passive"))
      (node (ref "R3") (pin "2") (pinfunction "2_2") (pintype "passive"))
    )
    (net (code "21") (name "GND") (class "Default")
      (node (ref "A1") (pin "5") (pinfunction "GND_5") (pintype "bidirectional"))
      (node (ref "A1") (pin "P$1") (pinfunction "MTG_1_P$1") (pintype "bidirectional"))
      (node (ref "A1") (pin "P$2") (pinfunction "MTG_2_P$2") (pintype "bidirectional"))
      (node (ref "A2") (pin "5") (pinfunction "GND_5") (pintype "bidirectional"))
      (node (ref "A2") (pin "P$1") (pinfunction "MTG_1_P$1") (pintype "bidirectional"))
      (node (ref "A2") (pin "P$2") (pinfunction "MTG_2_P$2") (pintype "bidirectional"))
      (node (ref "C1") (pin "2") (pinfunction "2_2") (pintype "passive"))
      (node (ref "C10") (pin "1") (pinfunction "1_1") (pintype "passive"))
      (node (ref "C11") (pin "2") (pinfunction "2_2") (pintype "passive"))
      (node (ref "C12") (pin "2") (pinfunction "2_2") (pintype "passive"))
      (node (ref "C13") (pin "2") (pinfunction "2_2") (pintype "passive"))
      (node (ref "C14") (pin "2") (pinfunction "2_2") (pintype "passive"))
      (node (ref "C15") (pin "2") (pinfunction "2_2") (pintype "passive"))
      (node (ref "C16") (pin "2") (pinfunction "2_2") (pintype "passive"))
      (node (ref "C19") (pin "2") (pinfunction "2_2") (pintype "passive"))
      (node (ref "C2") (pin "-") (pinfunction "-_-") (pintype "passive"))
      (node (ref "C20") (pin "2") (pinfunction "2_2") (pintype "passive"))
      (node (ref "C22") (pin "2") (pinfunction "2_2") (pintype "passive"))
      (node (ref "C24") (pin "1") (pinfunction "1_1") (pintype "passive"))
      (node (ref "C25") (pin "1") (pinfunction "1_1") (pintype "passive"))
      (node (ref "C26") (pin "1") (pinfunction "1_1") (pintype "passive"))
      (node (ref "C27") (pin "1") (pinfunction "1_1") (pintype "passive"))
      (node (ref "C28") (pin "1") (pinfunction "1_1") (pintype "passive"))
      (node (ref "C29") (pin "2") (pinfunction "2_2") (pintype "passive"))
      (node (ref "C3") (pin "1") (pinfunction "1_1") (pintype "passive"))
      (node (ref "C4") (pin "1") (pinfunction "1_1") (pintype "passive"))
      (node (ref "C5") (pin "1") (pinfunction "1_1") (pintype "passive"))
      (node (ref "C6") (pin "1") (pinfunction "1_1") (pintype "passive"))
      (node (ref "C7") (pin "2") (pinfunction "2_2") (pintype "passive"))
      (node (ref "C8") (pin "2") (pinfunction "2_2") (pintype "passive"))
      (node (ref "C9") (pin "2") (pinfunction "2_2") (pintype "passive"))
      (node (ref "J1") (pin "1") (pinfunction "GND_1") (pintype "bidirectional"))
      (node (ref "J6") (pin "3") (pinfunction "3_3") (pintype "passive"))
      (node (ref "J7") (pin "3") (pinfunction "GND_3") (pintype "bidirectional"))
      (node (ref "JP4") (pin "6") (pinfunction "6_6") (pintype "passive"))
      (node (ref "LED1") (pin "C") (pinfunction "C_C") (pintype "passive"))
      (node (ref "LED2") (pin "C") (pinfunction "C_C") (pintype "passive"))
      (node (ref "LED3") (pin "C") (pinfunction "C_C") (pintype "passive"))
      (node (ref "Q1") (pin "2") (pinfunction "S_2") (pintype "passive"))
      (node (ref "Q3") (pin "2") (pinfunction "S_2") (pintype "passive"))
      (node (ref "R11") (pin "2") (pinfunction "2_2") (pintype "passive"))
      (node (ref "R18") (pin "2") (pinfunction "2_2") (pintype "passive"))
      (node (ref "R19") (pin "1") (pinfunction "1_1") (pintype "passive"))
      (node (ref "R25") (pin "2") (pinfunction "2_2") (pintype "passive"))
      (node (ref "R3") (pin "1") (pinfunction "1_1") (pintype "passive"))
      (node (ref "R33") (pin "1") (pinfunction "1_1") (pintype "passive"))
      (node (ref "R36") (pin "1") (pinfunction "1_1") (pintype "passive"))
      (node (ref "R38") (pin "1") (pinfunction "1_1") (pintype "passive"))
      (node (ref "R42") (pin "2") (pinfunction "2_2") (pintype "passive"))
      (node (ref "R43") (pin "2") (pinfunction "2_2") (pintype "passive"))
      (node (ref "R45") (pin "2") (pinfunction "2_2") (pintype "passive"))
      (node (ref "R46") (pin "2") (pinfunction "2_2") (pintype "passive"))
      (node (ref "R47") (pin "2") (pinfunction "2_2") (pintype "passive"))
      (node (ref "R48") (pin "1") (pinfunction "1_1") (pintype "passive"))
      (node (ref "R49") (pin "1") (pinfunction "1_1") (pintype "passive"))
      (node (ref "R5") (pin "1") (pinfunction "1_1") (pintype "passive"))
      (node (ref "R50") (pin "1") (pinfunction "1_1") (pintype "passive"))
      (node (ref "R51") (pin "1") (pinfunction "1_1") (pintype "passive"))
      (node (ref "R52") (pin "1") (pinfunction "1_1") (pintype "passive"))
      (node (ref "R53") (pin "1") (pinfunction "1_1") (pintype "passive"))
      (node (ref "R54") (pin "1") (pinfunction "1_1") (pintype "passive"))
      (node (ref "R55") (pin "2") (pinfunction "2_2") (pintype "passive"))
      (node (ref "R56") (pin "1") (pinfunction "1_1") (pintype "passive"))
      (node (ref "R6") (pin "1") (pinfunction "1_1") (pintype "passive"))
      (node (ref "S1") (pin "3") (pinfunction "P_3") (pintype "passive"))
      (node (ref "S1") (pin "4") (pinfunction "P1_4") (pintype "passive"))
      (node (ref "U1") (pin "14") (pinfunction "AVSS1_14") (pintype "bidirectional"))
      (node (ref "U1") (pin "19") (pinfunction "DVSS1_19") (pintype "bidirectional"))
      (node (ref "U1") (pin "49") (pinfunction "DVSS2_49") (pintype "bidirectional"))
      (node (ref "U1") (pin "61") (pinfunction "VSSU_61") (pintype "bidirectional"))
      (node (ref "U1") (pin "65") (pinfunction "VBUS_65") (pintype "bidirectional"))
      (node (ref "U1") (pin "68") (pinfunction "AVSS2_68") (pintype "bidirectional"))
      (node (ref "U2") (pin "2") (pinfunction "V-_2") (pintype "bidirectional"))
      (node (ref "U3") (pin "10") (pinfunction "GND_10") (pintype "power_in"))
      (node (ref "U3") (pin "11") (pinfunction "MODE_11") (pintype "passive"))
      (node (ref "U3") (pin "6") (pinfunction "COM_6") (pintype "input"))
      (node (ref "U4") (pin "2") (pinfunction "V-_2") (pintype "bidirectional"))
      (node (ref "U5") (pin "2") (pinfunction "V-_2") (pintype "bidirectional"))
      (node (ref "U6") (pin "10") (pinfunction "PIN10(GND)_10") (pintype "bidirectional"))
      (node (ref "U6") (pin "15") (pinfunction "PIN15(GND)_15") (pintype "bidirectional"))
      (node (ref "U6") (pin "16") (pinfunction "PIN16(GND)_16") (pintype "bidirectional"))
      (node (ref "U6") (pin "17") (pinfunction "COM3/I2C_ADDR_17") (pintype "bidirectional"))
      (node (ref "U6") (pin "18") (pinfunction "COM2(GND)_18") (pintype "bidirectional"))
      (node (ref "U6") (pin "2") (pinfunction "GND_2") (pintype "power_in"))
      (node (ref "U6") (pin "25") (pinfunction "GND_25") (pintype "power_in"))
      (node (ref "U6") (pin "5") (pinfunction "PS1_5") (pintype "input"))
      (node (ref "U6") (pin "6") (pinfunction "PS0_6") (pintype "input"))
      (node (ref "U7") (pin "11") (pinfunction "GND(A)_11") (pintype "bidirectional"))
      (node (ref "U7") (pin "14") (pinfunction "GND(C)_14") (pintype "bidirectional"))
      (node (ref "U7") (pin "15") (pinfunction "OFF+(A,B,C)_15") (pintype "bidirectional"))
      (node (ref "U7") (pin "5") (pinfunction "GND(B)_5") (pintype "bidirectional"))
      (node (ref "U7") (pin "8") (pinfunction "S/R-(A,B,C)_8") (pintype "bidirectional"))
      (node (ref "Y1") (pin "P3") (pinfunction "GND_P3") (pintype "power_in"))
      (node (ref "Y2") (pin "2") (pinfunction "2_2") (pintype "passive"))
      (node (ref "Y3") (pin "P3") (pinfunction "GND_P3") (pintype "power_in"))
    )
    (net (code "22") (name "HMC1053_RESET") (class "Default")
      (node (ref "Q2") (pin "1") (pinfunction "G_1") (pintype "passive"))
      (node (ref "Q3") (pin "1") (pinfunction "G_1") (pintype "passive"))
      (node (ref "TP1") (pin "1") (pinfunction "TP_1") (pintype "input"))
      (node (ref "U1") (pin "1") (pinfunction "P6.4/CB4/A4_1") (pintype "bidirectional"))
    )
    (net (code "23") (name "MAG_X_FIN") (class "Default")
      (node (ref "J9") (pin "10") (pinfunction "10_10") (pintype "bidirectional"))
      (node (ref "U1") (pin "23") (pinfunction "P1.2/TA0.1_23") (pintype "bidirectional"))
    )
    (net (code "24") (name "MAG_X_RIN") (class "Default")
      (node (ref "J9") (pin "12") (pinfunction "12_12") (pintype "bidirectional"))
      (node (ref "U1") (pin "24") (pinfunction "P1.3/TA0.2_24") (pintype "bidirectional"))
    )
    (net (code "25") (name "MAG_Y_FIN") (class "Default")
      (node (ref "J9") (pin "6") (pinfunction "6_6") (pintype "bidirectional"))
      (node (ref "U1") (pin "29") (pinfunction "P2.0/TA1.1_29") (pintype "bidirectional"))
    )
    (net (code "26") (name "MAG_Y_RIN") (class "Default")
      (node (ref "J9") (pin "8") (pinfunction "8_8") (pintype "bidirectional"))
      (node (ref "U1") (pin "30") (pinfunction "P2.1/TA1.2_30") (pintype "bidirectional"))
    )
    (net (code "27") (name "MAG_Z_FIN") (class "Default")
      (node (ref "J9") (pin "2") (pinfunction "2_2") (pintype "bidirectional"))
      (node (ref "U1") (pin "25") (pinfunction "P1.4/TA0.3_25") (pintype "bidirectional"))
    )
    (net (code "28") (name "MAG_Z_RIN") (class "Default")
      (node (ref "J9") (pin "4") (pinfunction "4_4") (pintype "bidirectional"))
      (node (ref "U1") (pin "26") (pinfunction "P1.5/TA0.4_26") (pintype "bidirectional"))
    )
    (net (code "29") (name "MSP430_ACTIVE") (class "Default")
      (node (ref "J11") (pin "10") (pinfunction "10_10") (pintype "bidirectional"))
      (node (ref "R8") (pin "1") (pinfunction "1_1") (pintype "passive"))
      (node (ref "U1") (pin "77") (pinfunction "P6.0/CB0/A0_77") (pintype "bidirectional"))
    )
    (net (code "30") (name "MSP_OBC_RESET") (class "Default")
      (node (ref "J11") (pin "5") (pinfunction "5_5") (pintype "bidirectional"))
      (node (ref "Q1") (pin "1") (pinfunction "G_1") (pintype "passive"))
      (node (ref "R36") (pin "2") (pinfunction "2_2") (pintype "passive"))
    )
    (net (code "31") (name "Net-(J1-5V)") (class "Default")
      (node (ref "J1") (pin "2") (pinfunction "5V_2") (pintype "bidirectional"))
      (node (ref "R42") (pin "1") (pinfunction "1_1") (pintype "passive"))
    )
    (net (code "32") (name "Net-(J1-NC)") (class "Default")
      (node (ref "J1") (pin "10") (pinfunction "NC_10") (pintype "bidirectional"))
      (node (ref "R43") (pin "1") (pinfunction "1_1") (pintype "passive"))
    )
    (net (code "33") (name "Net-(J3-Pad8)") (class "Default")
      (node (ref "J3") (pin "8") (pinfunction "8_8") (pintype "bidirectional"))
      (node (ref "R45") (pin "1") (pinfunction "1_1") (pintype "passive"))
    )
    (net (code "34") (name "Net-(J8-Pad9)") (class "Default")
      (node (ref "J8") (pin "9") (pinfunction "9_9") (pintype "bidirectional"))
      (node (ref "R56") (pin "2") (pinfunction "2_2") (pintype "passive"))
    )
    (net (code "35") (name "Net-(J8-Pad10)") (class "Default")
      (node (ref "J8") (pin "10") (pinfunction "10_10") (pintype "bidirectional"))
      (node (ref "R55") (pin "1") (pinfunction "1_1") (pintype "passive"))
    )
    (net (code "36") (name "Net-(LED1-PadA)") (class "Default")
      (node (ref "LED1") (pin "A") (pinfunction "A_A") (pintype "passive"))
      (node (ref "R8") (pin "2") (pinfunction "2_2") (pintype "passive"))
    )
    (net (code "37") (name "Net-(LED2-PadA)") (class "Default")
      (node (ref "LED2") (pin "A") (pinfunction "A_A") (pintype "passive"))
      (node (ref "R31") (pin "2") (pinfunction "2_2") (pintype "passive"))
    )
    (net (code "38") (name "Net-(LED3-PadA)") (class "Default")
      (node (ref "LED3") (pin "A") (pinfunction "A_A") (pintype "passive"))
      (node (ref "R32") (pin "2") (pinfunction "2_2") (pintype "passive"))
    )
    (net (code "39") (name "Net-(Q2-D)") (class "Default")
      (node (ref "C18") (pin "1") (pinfunction "1_1") (pintype "passive"))
      (node (ref "Q2") (pin "3") (pinfunction "D_3") (pintype "passive"))
      (node (ref "Q3") (pin "3") (pinfunction "D_3") (pintype "passive"))
      (node (ref "TP6") (pin "1") (pinfunction "TP_1") (pintype "input"))
    )
    (net (code "40") (name "Net-(Q2-S)") (class "Default")
      (node (ref "C10") (pin "2") (pinfunction "2_2") (pintype "passive"))
      (node (ref "Q2") (pin "2") (pinfunction "S_2") (pintype "passive"))
      (node (ref "R9") (pin "1") (pinfunction "1_1") (pintype "passive"))
    )
    (net (code "41") (name "Net-(R10-Pad2)") (class "Default")
      (node (ref "R10") (pin "2") (pinfunction "2_2") (pintype "passive"))
      (node (ref "R11") (pin "1") (pinfunction "1_1") (pintype "passive"))
      (node (ref "R14") (pin "1") (pinfunction "1_1") (pintype "passive"))
    )
    (net (code "42") (name "Net-(R17-Pad2)") (class "Default")
      (node (ref "R17") (pin "2") (pinfunction "2_2") (pintype "passive"))
      (node (ref "R18") (pin "1") (pinfunction "1_1") (pintype "passive"))
      (node (ref "R22") (pin "1") (pinfunction "1_1") (pintype "passive"))
    )
    (net (code "43") (name "Net-(R24-Pad2)") (class "Default")
      (node (ref "R24") (pin "2") (pinfunction "2_2") (pintype "passive"))
      (node (ref "R25") (pin "1") (pinfunction "1_1") (pintype "passive"))
      (node (ref "R28") (pin "1") (pinfunction "1_1") (pintype "passive"))
    )
    (net (code "44") (name "Net-(TP5-TP)") (class "Default")
      (node (ref "R33") (pin "2") (pinfunction "2_2") (pintype "passive"))
      (node (ref "TP5") (pin "1") (pinfunction "TP_1") (pintype "input"))
      (node (ref "U3") (pin "2") (pinfunction "CH0_2") (pintype "input"))
    )
    (net (code "45") (name "Net-(TP7-TP)") (class "Default")
      (node (ref "R16") (pin "2") (pinfunction "2_2") (pintype "passive"))
      (node (ref "TP7") (pin "1") (pinfunction "TP_1") (pintype "input"))
      (node (ref "U7") (pin "3") (pinfunction "S/R+(A,B)_3") (pintype "bidirectional"))
      (node (ref "U7") (pin "6") (pinfunction "S/R+(C)_6") (pintype "bidirectional"))
    )
    (net (code "46") (name "Net-(TP8-TP)") (class "Default")
      (node (ref "C18") (pin "2") (pinfunction "2_2") (pintype "passive"))
      (node (ref "R16") (pin "1") (pinfunction "1_1") (pintype "passive"))
      (node (ref "TP8") (pin "1") (pinfunction "TP_1") (pintype "input"))
    )
    (net (code "47") (name "Net-(U1-AVCC1)") (class "Default")
      (node (ref "C1") (pin "1") (pinfunction "1_1") (pintype "passive"))
      (node (ref "R1") (pin "1") (pinfunction "1_1") (pintype "passive"))
      (node (ref "U1") (pin "11") (pinfunction "AVCC1_11") (pintype "bidirectional"))
    )
    (net (code "48") (name "Net-(U1-P5.2{slash}XT2IN)") (class "Default")
      (node (ref "U1") (pin "69") (pinfunction "P5.2/XT2IN_69") (pintype "bidirectional"))
      (node (ref "Y2") (pin "3") (pinfunction "3_3") (pintype "passive"))
    )
    (net (code "49") (name "Net-(U1-P5.3{slash}XT2OUT)") (class "Default")
      (node (ref "U1") (pin "70") (pinfunction "P5.3/XT2OUT_70") (pintype "bidirectional"))
      (node (ref "Y2") (pin "1") (pinfunction "1_1") (pintype "passive"))
    )
    (net (code "50") (name "Net-(U1-P5.4{slash}XIN)") (class "Default")
      (node (ref "C3") (pin "2") (pinfunction "2_2") (pintype "passive"))
      (node (ref "U1") (pin "12") (pinfunction "P5.4/XIN_12") (pintype "bidirectional"))
      (node (ref "Y1") (pin "P2") (pinfunction "2_P2") (pintype "bidirectional"))
    )
    (net (code "51") (name "Net-(U1-P5.5{slash}XOUT)") (class "Default")
      (node (ref "C4") (pin "2") (pinfunction "2_2") (pintype "passive"))
      (node (ref "U1") (pin "13") (pinfunction "P5.5/XOUT_13") (pintype "bidirectional"))
      (node (ref "Y1") (pin "P1") (pinfunction "1_P1") (pintype "bidirectional"))
    )
    (net (code "52") (name "Net-(U1-PUR)") (class "Default")
      (node (ref "R6") (pin "2") (pinfunction "2_2") (pintype "passive"))
      (node (ref "U1") (pin "63") (pinfunction "PUR_63") (pintype "bidirectional"))
    )
    (net (code "53") (name "Net-(U1-V1.8)") (class "Default")
      (node (ref "R46") (pin "1") (pinfunction "1_1") (pintype "passive"))
      (node (ref "U1") (pin "67") (pinfunction "V1.8_67") (pintype "bidirectional"))
    )
    (net (code "54") (name "Net-(U1-VCORE)") (class "Default")
      (node (ref "C6") (pin "2") (pinfunction "2_2") (pintype "passive"))
      (node (ref "U1") (pin "20") (pinfunction "VCORE_20") (pintype "bidirectional"))
    )
    (net (code "55") (name "Net-(U1-VUSB)") (class "Default")
      (node (ref "R47") (pin "1") (pinfunction "1_1") (pintype "passive"))
      (node (ref "U1") (pin "66") (pinfunction "VUSB_66") (pintype "bidirectional"))
    )
    (net (code "56") (name "Net-(U2-+)") (class "Default")
      (node (ref "R12") (pin "1") (pinfunction "1_1") (pintype "passive"))
      (node (ref "R14") (pin "2") (pinfunction "2_2") (pintype "passive"))
      (node (ref "U2") (pin "1") (pinfunction "+_1") (pintype "bidirectional"))
    )
    (net (code "57") (name "Net-(U2--)") (class "Default")
      (node (ref "C17") (pin "1") (pinfunction "1_1") (pintype "passive"))
      (node (ref "R13") (pin "1") (pinfunction "1_1") (pintype "passive"))
      (node (ref "R15") (pin "2") (pinfunction "2_2") (pintype "passive"))
      (node (ref "U2") (pin "3") (pinfunction "-_3") (pintype "bidirectional"))
    )
    (net (code "58") (name "Net-(U3-BUSY)") (class "Default")
      (node (ref "R38") (pin "2") (pinfunction "2_2") (pintype "passive"))
      (node (ref "U3") (pin "13") (pinfunction "BUSY_13") (pintype "output"))
    )
    (net (code "59") (name "Net-(U3-~{SHDN})") (class "Default")
      (node (ref "C29") (pin "1") (pinfunction "1_1") (pintype "passive"))
      (node (ref "R37") (pin "2") (pinfunction "2_2") (pintype "passive"))
      (node (ref "U3") (pin "7") (pinfunction "~{SHDN}_7") (pintype "passive"))
    )
    (net (code "60") (name "Net-(U4-+)") (class "Default")
      (node (ref "R20") (pin "1") (pinfunction "1_1") (pintype "passive"))
      (node (ref "R22") (pin "2") (pinfunction "2_2") (pintype "passive"))
      (node (ref "U4") (pin "1") (pinfunction "+_1") (pintype "bidirectional"))
    )
    (net (code "61") (name "Net-(U4--)") (class "Default")
      (node (ref "C21") (pin "1") (pinfunction "1_1") (pintype "passive"))
      (node (ref "R21") (pin "1") (pinfunction "1_1") (pintype "passive"))
      (node (ref "R23") (pin "2") (pinfunction "2_2") (pintype "passive"))
      (node (ref "U4") (pin "3") (pinfunction "-_3") (pintype "bidirectional"))
    )
    (net (code "62") (name "Net-(U5-+)") (class "Default")
      (node (ref "R26") (pin "1") (pinfunction "1_1") (pintype "passive"))
      (node (ref "R28") (pin "2") (pinfunction "2_2") (pintype "passive"))
      (node (ref "U5") (pin "1") (pinfunction "+_1") (pintype "bidirectional"))
    )
    (net (code "63") (name "Net-(U5--)") (class "Default")
      (node (ref "C23") (pin "1") (pinfunction "1_1") (pintype "passive"))
      (node (ref "R27") (pin "1") (pinfunction "1_1") (pintype "passive"))
      (node (ref "R29") (pin "2") (pinfunction "2_2") (pintype "passive"))
      (node (ref "U5") (pin "3") (pinfunction "-_3") (pintype "bidirectional"))
    )
    (net (code "64") (name "Net-(U6-CAP)") (class "Default")
      (node (ref "C24") (pin "2") (pinfunction "2_2") (pintype "passive"))
      (node (ref "U6") (pin "9") (pinfunction "CAP_9") (pintype "passive"))
    )
    (net (code "65") (name "Net-(U6-NC_1)") (class "Default")
      (node (ref "R48") (pin "2") (pinfunction "2_2") (pintype "passive"))
      (node (ref "U6") (pin "1") (pinfunction "NC_1_1") (pintype "bidirectional"))
    )
    (net (code "66") (name "Net-(U6-NC_2)") (class "Default")
      (node (ref "R49") (pin "2") (pinfunction "2_2") (pintype "passive"))
      (node (ref "U6") (pin "12") (pinfunction "NC_2_12") (pintype "bidirectional"))
    )
    (net (code "67") (name "Net-(U6-NC_3)") (class "Default")
      (node (ref "R50") (pin "2") (pinfunction "2_2") (pintype "passive"))
      (node (ref "U6") (pin "13") (pinfunction "NC_3_13") (pintype "bidirectional"))
    )
    (net (code "68") (name "Net-(U6-NC_4)") (class "Default")
      (node (ref "R51") (pin "2") (pinfunction "2_2") (pintype "passive"))
      (node (ref "U6") (pin "21") (pinfunction "NC_4_21") (pintype "bidirectional"))
    )
    (net (code "69") (name "Net-(U6-NC_5)") (class "Default")
      (node (ref "R52") (pin "2") (pinfunction "2_2") (pintype "passive"))
      (node (ref "U6") (pin "22") (pinfunction "NC_5_22") (pintype "bidirectional"))
    )
    (net (code "70") (name "Net-(U6-NC_6)") (class "Default")
      (node (ref "R53") (pin "2") (pinfunction "2_2") (pintype "passive"))
      (node (ref "U6") (pin "23") (pinfunction "NC_6_23") (pintype "bidirectional"))
    )
    (net (code "71") (name "Net-(U6-NC_7)") (class "Default")
      (node (ref "R54") (pin "2") (pinfunction "2_2") (pintype "passive"))
      (node (ref "U6") (pin "24") (pinfunction "NC_7_24") (pintype "bidirectional"))
    )
    (net (code "72") (name "Net-(U6-PIN7(SWDIO))") (class "Default")
      (node (ref "J2") (pin "1") (pinfunction "1_1") (pintype "passive"))
      (node (ref "U6") (pin "7") (pinfunction "PIN7(SWDIO)_7") (pintype "bidirectional"))
    )
    (net (code "73") (name "Net-(U6-PIN8(SWCLK))") (class "Default")
      (node (ref "J2") (pin "2") (pinfunction "2_2") (pintype "passive"))
      (node (ref "U6") (pin "8") (pinfunction "PIN8(SWCLK)_8") (pintype "bidirectional"))
    )
    (net (code "74") (name "Net-(U6-XIN32)") (class "Default")
      (node (ref "C26") (pin "2") (pinfunction "2_2") (pintype "passive"))
      (node (ref "U6") (pin "27") (pinfunction "XIN32_27") (pintype "input"))
      (node (ref "Y3") (pin "P1") (pinfunction "1_P1") (pintype "bidirectional"))
    )
    (net (code "75") (name "Net-(U6-XOUT32)") (class "Default")
      (node (ref "C27") (pin "2") (pinfunction "2_2") (pintype "passive"))
      (node (ref "U6") (pin "26") (pinfunction "XOUT32_26") (pintype "output"))
      (node (ref "Y3") (pin "P2") (pinfunction "2_P2") (pintype "bidirectional"))
    )
    (net (code "76") (name "Net-(U6-~{BOOT_LOAD_PIN})") (class "Default")
      (node (ref "R30") (pin "1") (pinfunction "1_1") (pintype "passive"))
      (node (ref "U6") (pin "4") (pinfunction "~{BOOT_LOAD_PIN}_4") (pintype "bidirectional"))
    )
    (net (code "77") (name "Net-(U7-OFF-(A,B))") (class "Default")
      (node (ref "R19") (pin "2") (pinfunction "2_2") (pintype "passive"))
      (node (ref "U7") (pin "2") (pinfunction "OFF-(A,B)_2") (pintype "bidirectional"))
      (node (ref "U7") (pin "7") (pinfunction "OFF-(C)_7") (pintype "bidirectional"))
    )
    (net (code "78") (name "OUT_A_N") (class "Default")
      (node (ref "R12") (pin "2") (pinfunction "2_2") (pintype "passive"))
      (node (ref "TP13") (pin "1") (pinfunction "TP_1") (pintype "input"))
      (node (ref "U7") (pin "10") (pinfunction "OUT-(A)_10") (pintype "bidirectional"))
    )
    (net (code "79") (name "OUT_A_P") (class "Default")
      (node (ref "R13") (pin "2") (pinfunction "2_2") (pintype "passive"))
      (node (ref "TP12") (pin "1") (pinfunction "TP_1") (pintype "input"))
      (node (ref "U7") (pin "16") (pinfunction "OUT+(A)_16") (pintype "bidirectional"))
    )
    (net (code "80") (name "OUT_B_N") (class "Default")
      (node (ref "R20") (pin "2") (pinfunction "2_2") (pintype "passive"))
      (node (ref "TP15") (pin "1") (pinfunction "TP_1") (pintype "input"))
      (node (ref "U7") (pin "4") (pinfunction "OUT-(B)_4") (pintype "bidirectional"))
    )
    (net (code "81") (name "OUT_B_P") (class "Default")
      (node (ref "R21") (pin "2") (pinfunction "2_2") (pintype "passive"))
      (node (ref "TP14") (pin "1") (pinfunction "TP_1") (pintype "input"))
      (node (ref "U7") (pin "12") (pinfunction "OUT+(B)_12") (pintype "bidirectional"))
    )
    (net (code "82") (name "OUT_C_N") (class "Default")
      (node (ref "R26") (pin "2") (pinfunction "2_2") (pintype "passive"))
      (node (ref "TP17") (pin "1") (pinfunction "TP_1") (pintype "input"))
      (node (ref "U7") (pin "9") (pinfunction "OUT-(C)_9") (pintype "bidirectional"))
    )
    (net (code "83") (name "OUT_C_P") (class "Default")
      (node (ref "R27") (pin "2") (pinfunction "2_2") (pintype "passive"))
      (node (ref "TP16") (pin "1") (pinfunction "TP_1") (pintype "input"))
      (node (ref "U7") (pin "13") (pinfunction "OUT+(C)_13") (pintype "bidirectional"))
    )
    (net (code "84") (name "P1.0") (class "Default")
      (node (ref "JP1") (pin "1") (pinfunction "1_1") (pintype "passive"))
      (node (ref "U1") (pin "21") (pinfunction "P1.0/TA0CLK/ACLK_21") (pintype "bidirectional"))
    )
    (net (code "85") (name "P1.1") (class "Default")
      (node (ref "JP1") (pin "2") (pinfunction "2_2") (pintype "passive"))
      (node (ref "U1") (pin "22") (pinfunction "P1.1/TA0.0_22") (pintype "bidirectional"))
    )
    (net (code "86") (name "P1.7{slash}CTS") (class "Default")
      (node (ref "J1") (pin "5") (pinfunction "CTS_5") (pintype "bidirectional"))
      (node (ref "U1") (pin "28") (pinfunction "P1.7/TA1.0_28") (pintype "bidirectional"))
    )
    (net (code "87") (name "P2.3") (class "Default")
      (node (ref "JP1") (pin "3") (pinfunction "3_3") (pintype "passive"))
      (node (ref "U1") (pin "32") (pinfunction "P2.3/TA2.0_32") (pintype "bidirectional"))
    )
    (net (code "88") (name "P4.4{slash}UCA1TXD") (class "Default")
      (node (ref "J1") (pin "7") (pinfunction "TXD_7") (pintype "bidirectional"))
      (node (ref "U1") (pin "51") (pinfunction "P4.4/PM_UCA1TXD/PM_UCA1SIMO_51") (pintype "bidirectional"))
    )
    (net (code "89") (name "P4.5{slash}UCA1RXD") (class "Default")
      (node (ref "J1") (pin "6") (pinfunction "RXD_6") (pintype "bidirectional"))
      (node (ref "U1") (pin "52") (pinfunction "P4.5/PM_UCA1RXD/PM_UCA1SOMI_52") (pintype "bidirectional"))
    )
    (net (code "90") (name "P6.7{slash}RTS") (class "Default")
      (node (ref "J1") (pin "4") (pinfunction "RTS_4") (pintype "bidirectional"))
      (node (ref "U1") (pin "4") (pinfunction "P6.7/CB7/A7_4") (pintype "bidirectional"))
    )
    (net (code "91") (name "RESERVED_1") (class "Default")
      (node (ref "J11") (pin "6") (pinfunction "6_6") (pintype "bidirectional"))
      (node (ref "U1") (pin "31") (pinfunction "P2.2/TA2CLK/SMCLK_31") (pintype "bidirectional"))
    )
    (net (code "92") (name "RESERVED_2") (class "Default")
      (node (ref "J11") (pin "8") (pinfunction "8_8") (pintype "bidirectional"))
      (node (ref "U1") (pin "35") (pinfunction "P2.6/RTCCLK/DMAE0_35") (pintype "bidirectional"))
    )
    (net (code "93") (name "RST{slash}SBWTDIO") (class "Default")
      (node (ref "C7") (pin "1") (pinfunction "1_1") (pintype "passive"))
      (node (ref "J1") (pin "8") (pinfunction "SBWTDIO_8") (pintype "bidirectional"))
      (node (ref "Q1") (pin "3") (pinfunction "D_3") (pintype "passive"))
      (node (ref "R7") (pin "1") (pinfunction "1_1") (pintype "passive"))
      (node (ref "S1") (pin "1") (pinfunction "S_1") (pintype "passive"))
      (node (ref "S1") (pin "2") (pinfunction "S1_2") (pintype "passive"))
      (node (ref "U1") (pin "76") (pinfunction "RST/NMI/SBWTDIO_76") (pintype "bidirectional"))
    )
    (net (code "94") (name "RW_X_DIR") (class "Default")
      (node (ref "J9") (pin "7") (pinfunction "7_7") (pintype "bidirectional"))
      (node (ref "U1") (pin "75") (pinfunction "PJ.3/TCK_75") (pintype "bidirectional"))
    )
    (net (code "95") (name "RW_X_OUTFG") (class "Default")
      (node (ref "J9") (pin "13") (pinfunction "13_13") (pintype "bidirectional"))
      (node (ref "U1") (pin "57") (pinfunction "P7.4/TB0.2_57") (pintype "bidirectional"))
    )
    (net (code "96") (name "RW_X_SPEED_CTRL") (class "Default")
      (node (ref "J9") (pin "1") (pinfunction "1_1") (pintype "bidirectional"))
      (node (ref "U1") (pin "42") (pinfunction "P3.5/TB0.5_42") (pintype "bidirectional"))
    )
    (net (code "97") (name "RW_Y_DIR") (class "Default")
      (node (ref "J9") (pin "9") (pinfunction "9_9") (pintype "bidirectional"))
      (node (ref "U1") (pin "74") (pinfunction "PJ.2/TMS_74") (pintype "bidirectional"))
    )
    (net (code "98") (name "RW_Y_OUTFG") (class "Default")
      (node (ref "J8") (pin "1") (pinfunction "1_1") (pintype "bidirectional"))
      (node (ref "U1") (pin "56") (pinfunction "P5.7/TB0.1_56") (pintype "bidirectional"))
    )
    (net (code "99") (name "RW_Y_SPEED_CTRL") (class "Default")
      (node (ref "J9") (pin "3") (pinfunction "3_3") (pintype "bidirectional"))
      (node (ref "U1") (pin "33") (pinfunction "P2.4/TA2.1_33") (pintype "bidirectional"))
    )
    (net (code "100") (name "RW_Z_DIR") (class "Default")
      (node (ref "J9") (pin "11") (pinfunction "11_11") (pintype "bidirectional"))
      (node (ref "U1") (pin "73") (pinfunction "PJ.1/TDI/TCLK_73") (pintype "bidirectional"))
    )
    (net (code "101") (name "RW_Z_OUTFG") (class "Default")
      (node (ref "J8") (pin "2") (pinfunction "2_2") (pintype "bidirectional"))
      (node (ref "U1") (pin "43") (pinfunction "P3.6/TB0.6_43") (pintype "bidirectional"))
    )
    (net (code "102") (name "RW_Z_SPEED_CTRL") (class "Default")
      (node (ref "J9") (pin "5") (pinfunction "5_5") (pintype "bidirectional"))
      (node (ref "U1") (pin "34") (pinfunction "P2.5/TA2.2_34") (pintype "bidirectional"))
    )
    (net (code "103") (name "TB0.3") (class "Default")
      (node (ref "JP1") (pin "4") (pinfunction "4_4") (pintype "passive"))
      (node (ref "U1") (pin "58") (pinfunction "P7.5/TB0.3_58") (pintype "bidirectional"))
    )
    (net (code "104") (name "TB0.4") (class "Default")
      (node (ref "JP1") (pin "5") (pinfunction "5_5") (pintype "passive"))
      (node (ref "U1") (pin "59") (pinfunction "P7.6/TB0.4_59") (pintype "bidirectional"))
    )
    (net (code "105") (name "TEST{slash}SBWTCK") (class "Default")
      (node (ref "J1") (pin "9") (pinfunction "SBWTCK_9") (pintype "bidirectional"))
      (node (ref "U1") (pin "71") (pinfunction "TEST/SBWTCK_71") (pintype "bidirectional"))
    )
    (net (code "106") (name "UCA0RXD") (class "Default")
      (node (ref "J11") (pin "1") (pinfunction "1_1") (pintype "bidirectional"))
      (node (ref "J4") (pin "2") (pinfunction "2_2") (pintype "passive"))
      (node (ref "U1") (pin "41") (pinfunction "P3.4/UCA0RXD/UCA0SOMI_41") (pintype "bidirectional"))
    )
    (net (code "107") (name "UCA0TXD") (class "Default")
      (node (ref "J11") (pin "3") (pinfunction "3_3") (pintype "bidirectional"))
      (node (ref "J4") (pin "1") (pinfunction "1_1") (pintype "passive"))
      (node (ref "U1") (pin "40") (pinfunction "P3.3/UCA0TXD/UCA0SIMO_40") (pintype "bidirectional"))
    )
    (net (code "108") (name "UCB0_SPI_CLK") (class "Default")
      (node (ref "J3") (pin "5") (pinfunction "5_5") (pintype "bidirectional"))
      (node (ref "J8") (pin "4") (pinfunction "4_4") (pintype "bidirectional"))
      (node (ref "JP4") (pin "5") (pinfunction "5_5") (pintype "passive"))
      (node (ref "U1") (pin "39") (pinfunction "P3.2/UCB0CLK/UCA0STE_39") (pintype "bidirectional"))
      (node (ref "U3") (pin "16") (pinfunction "DCLK_16") (pintype "input"))
    )
    (net (code "109") (name "UCB0_SPI_MISO") (class "Default")
      (node (ref "J3") (pin "1") (pinfunction "1_1") (pintype "bidirectional"))
      (node (ref "J8") (pin "6") (pinfunction "6_6") (pintype "bidirectional"))
      (node (ref "JP4") (pin "2") (pinfunction "2_2") (pintype "passive"))
      (node (ref "U1") (pin "38") (pinfunction "P3.1/UCB0SOMI/UCB0SCL_38") (pintype "bidirectional"))
      (node (ref "U3") (pin "12") (pinfunction "DOUT_12") (pintype "output"))
    )
    (net (code "110") (name "UCB0_SPI_MOSI") (class "Default")
      (node (ref "J3") (pin "3") (pinfunction "3_3") (pintype "bidirectional"))
      (node (ref "J8") (pin "8") (pinfunction "8_8") (pintype "bidirectional"))
      (node (ref "JP4") (pin "3") (pinfunction "3_3") (pintype "passive"))
      (node (ref "U1") (pin "37") (pinfunction "P3.0/UCB0SIMO/UCB0SDA_37") (pintype "bidirectional"))
      (node (ref "U3") (pin "14") (pinfunction "DIN_14") (pintype "input"))
    )
    (net (code "111") (name "UCB1_I2C_SCL") (class "Default")
      (node (ref "R40") (pin "1") (pinfunction "1_1") (pintype "passive"))
      (node (ref "TP18") (pin "1") (pinfunction "TP_1") (pintype "input"))
      (node (ref "U1") (pin "47") (pinfunction "P4.2/PM_UCB1SOMI/PM_UCB1SCL_47") (pintype "bidirectional"))
      (node (ref "U6") (pin "19") (pinfunction "COM1/SCL/RX_19") (pintype "bidirectional"))
    )
    (net (code "112") (name "UCB1_I2C_SDA") (class "Default")
      (node (ref "R39") (pin "1") (pinfunction "1_1") (pintype "passive"))
      (node (ref "TP19") (pin "1") (pinfunction "TP_1") (pintype "input"))
      (node (ref "U1") (pin "46") (pinfunction "P4.1/PM_UCB1SIMO/PM_UCB1SDA_46") (pintype "bidirectional"))
      (node (ref "U6") (pin "20") (pinfunction "COM0/SDA/TX_20") (pintype "bidirectional"))
    )
    (net (code "113") (name "Z-_SUN_3V_PRESENT") (class "Default")
      (node (ref "J11") (pin "9") (pinfunction "9_9") (pintype "bidirectional"))
      (node (ref "J3") (pin "10") (pinfunction "10_10") (pintype "bidirectional"))
    )
    (net (code "114") (name "unconnected-(H1-MOUNT-PadB3,2)") (class "Default")
      (node (ref "H1") (pin "B3,2") (pinfunction "MOUNT_B3,2") (pintype "passive"))
    )
    (net (code "115") (name "unconnected-(H2-MOUNT-PadB3,2)") (class "Default")
      (node (ref "H2") (pin "B3,2") (pinfunction "MOUNT_B3,2") (pintype "passive"))
    )
    (net (code "116") (name "unconnected-(H3-MOUNT-PadB3,2)") (class "Default")
      (node (ref "H3") (pin "B3,2") (pinfunction "MOUNT_B3,2") (pintype "passive"))
    )
    (net (code "117") (name "unconnected-(H4-MOUNT-PadB3,2)") (class "Default")
      (node (ref "H4") (pin "B3,2") (pinfunction "MOUNT_B3,2") (pintype "passive"))
    )
    (net (code "118") (name "unconnected-(MH1-MOUNT-Pad1)") (class "Default")
      (node (ref "MH1") (pin "1") (pinfunction "MOUNT_1") (pintype "no_connect"))
    )
    (net (code "119") (name "unconnected-(MH2-MOUNT-Pad1)") (class "Default")
      (node (ref "MH2") (pin "1") (pinfunction "MOUNT_1") (pintype "no_connect"))
    )
    (net (code "120") (name "unconnected-(MH3-MOUNT-Pad1)") (class "Default")
      (node (ref "MH3") (pin "1") (pinfunction "MOUNT_1") (pintype "no_connect"))
    )
    (net (code "121") (name "unconnected-(MH4-MOUNT-Pad1)") (class "Default")
      (node (ref "MH4") (pin "1") (pinfunction "MOUNT_1") (pintype "no_connect"))
    )
    (net (code "122") (name "unconnected-(U1-P3.7{slash}TB0OUTH{slash}SVMOUT-Pad44)") (class "Default")
      (node (ref "U1") (pin "44") (pinfunction "P3.7/TB0OUTH/SVMOUT_44") (pintype "bidirectional"))
    )
    (net (code "123") (name "unconnected-(U1-P4.0{slash}PM_UCB1STE{slash}PM_UCA1CLK-Pad45)") (class "Default")
      (node (ref "U1") (pin "45") (pinfunction "P4.0/PM_UCB1STE/PM_UCA1CLK_45") (pintype "bidirectional"))
    )
    (net (code "124") (name "unconnected-(U1-P4.6{slash}PM_NONE-Pad53)") (class "Default")
      (node (ref "U1") (pin "53") (pinfunction "P4.6/PM_NONE_53") (pintype "bidirectional"))
    )
    (net (code "125") (name "unconnected-(U1-P4.7{slash}PM_NONE-Pad54)") (class "Default")
      (node (ref "U1") (pin "54") (pinfunction "P4.7/PM_NONE_54") (pintype "bidirectional"))
    )
    (net (code "126") (name "unconnected-(U1-P5.6{slash}TB0.0-Pad55)") (class "Default")
      (node (ref "U1") (pin "55") (pinfunction "P5.6/TB0.0_55") (pintype "bidirectional"))
    )
    (net (code "127") (name "unconnected-(U1-P6.1{slash}CB1{slash}A1-Pad78)") (class "Default")
      (node (ref "U1") (pin "78") (pinfunction "P6.1/CB1/A1_78") (pintype "bidirectional"))
    )
    (net (code "128") (name "unconnected-(U1-P6.2{slash}CB2{slash}A2-Pad79)") (class "Default")
      (node (ref "U1") (pin "79") (pinfunction "P6.2/CB2/A2_79") (pintype "bidirectional"))
    )
    (net (code "129") (name "unconnected-(U1-P7.0{slash}CB8{slash}A12-Pad5)") (class "Default")
      (node (ref "U1") (pin "5") (pinfunction "P7.0/CB8/A12_5") (pintype "bidirectional"))
    )
    (net (code "130") (name "unconnected-(U1-P7.1{slash}CB9{slash}A13-Pad6)") (class "Default")
      (node (ref "U1") (pin "6") (pinfunction "P7.1/CB9/A13_6") (pintype "bidirectional"))
    )
    (net (code "131") (name "unconnected-(U1-P7.2{slash}CB10{slash}A14-Pad7)") (class "Default")
      (node (ref "U1") (pin "7") (pinfunction "P7.2/CB10/A14_7") (pintype "bidirectional"))
    )
    (net (code "132") (name "unconnected-(U1-P7.3{slash}CB11{slash}A15-Pad8)") (class "Default")
      (node (ref "U1") (pin "8") (pinfunction "P7.3/CB11/A15_8") (pintype "bidirectional"))
    )
    (net (code "133") (name "unconnected-(U1-P7.7{slash}TB0CLK{slash}MCLK-Pad60)") (class "Default")
      (node (ref "U1") (pin "60") (pinfunction "P7.7/TB0CLK/MCLK_60") (pintype "bidirectional"))
    )
    (net (code "134") (name "unconnected-(U1-PJ.0{slash}TDO-Pad72)") (class "Default")
      (node (ref "U1") (pin "72") (pinfunction "PJ.0/TDO_72") (pintype "bidirectional"))
    )
    (net (code "135") (name "unconnected-(U1-PU.0{slash}DP-Pad62)") (class "Default")
      (node (ref "U1") (pin "62") (pinfunction "PU.0/DP_62") (pintype "bidirectional"))
    )
    (net (code "136") (name "unconnected-(U1-PU.1{slash}DM-Pad64)") (class "Default")
      (node (ref "U1") (pin "64") (pinfunction "PU.1/DM_64") (pintype "bidirectional"))
    )
    (net (code "137") (name "~{CS}_CURR_SENSE_MTQR") (class "Default")
      (node (ref "J8") (pin "5") (pinfunction "5_5") (pintype "bidirectional"))
      (node (ref "U1") (pin "10") (pinfunction "P5.1/A9/VREF-/VEREF-_10") (pintype "bidirectional"))
    )
    (net (code "138") (name "~{CS}_CURR_SENSE_RW") (class "Default")
      (node (ref "J8") (pin "3") (pinfunction "3_3") (pintype "bidirectional"))
      (node (ref "U1") (pin "9") (pinfunction "P5.0/A8/VREF+/VEREF+_9") (pintype "bidirectional"))
    )
    (net (code "139") (name "~{CS}_HMC1053") (class "Default")
      (node (ref "TP2") (pin "1") (pinfunction "TP_1") (pintype "input"))
      (node (ref "U1") (pin "36") (pinfunction "P2.7/UCB0STE/UCA0CLK_36") (pintype "bidirectional"))
      (node (ref "U3") (pin "15") (pinfunction "~{CS}_15") (pintype "input"))
    )
    (net (code "140") (name "~{CS}_SUN_X+") (class "Default")
      (node (ref "J3") (pin "2") (pinfunction "2_2") (pintype "bidirectional"))
      (node (ref "U1") (pin "48") (pinfunction "P4.3/PM_UCB1CLK/PM_UCA1STE_48") (pintype "bidirectional"))
    )
    (net (code "141") (name "~{CS}_SUN_X-") (class "Default")
      (node (ref "J3") (pin "7") (pinfunction "7_7") (pintype "bidirectional"))
      (node (ref "U1") (pin "15") (pinfunction "P8.0_15") (pintype "bidirectional"))
    )
    (net (code "142") (name "~{CS}_SUN_Y+") (class "Default")
      (node (ref "J3") (pin "4") (pinfunction "4_4") (pintype "bidirectional"))
      (node (ref "U1") (pin "2") (pinfunction "P6.5/CB5/A5_2") (pintype "bidirectional"))
    )
    (net (code "143") (name "~{CS}_SUN_Y-") (class "Default")
      (node (ref "J3") (pin "9") (pinfunction "9_9") (pintype "bidirectional"))
      (node (ref "U1") (pin "16") (pinfunction "P8.1_16") (pintype "bidirectional"))
    )
    (net (code "144") (name "~{CS}_SUN_Z+") (class "Default")
      (node (ref "JP4") (pin "4") (pinfunction "4_4") (pintype "passive"))
      (node (ref "U1") (pin "3") (pinfunction "P6.6/CB6/A6_3") (pintype "bidirectional"))
    )
    (net (code "145") (name "~{CS}_SUN_Z-") (class "Default")
      (node (ref "J3") (pin "6") (pinfunction "6_6") (pintype "bidirectional"))
      (node (ref "U1") (pin "17") (pinfunction "P8.2_17") (pintype "bidirectional"))
    )
  )
)
